# ES_Daisy_Patch_Rev4.net
KiCad netlist of a schematic drawn in EAGLE
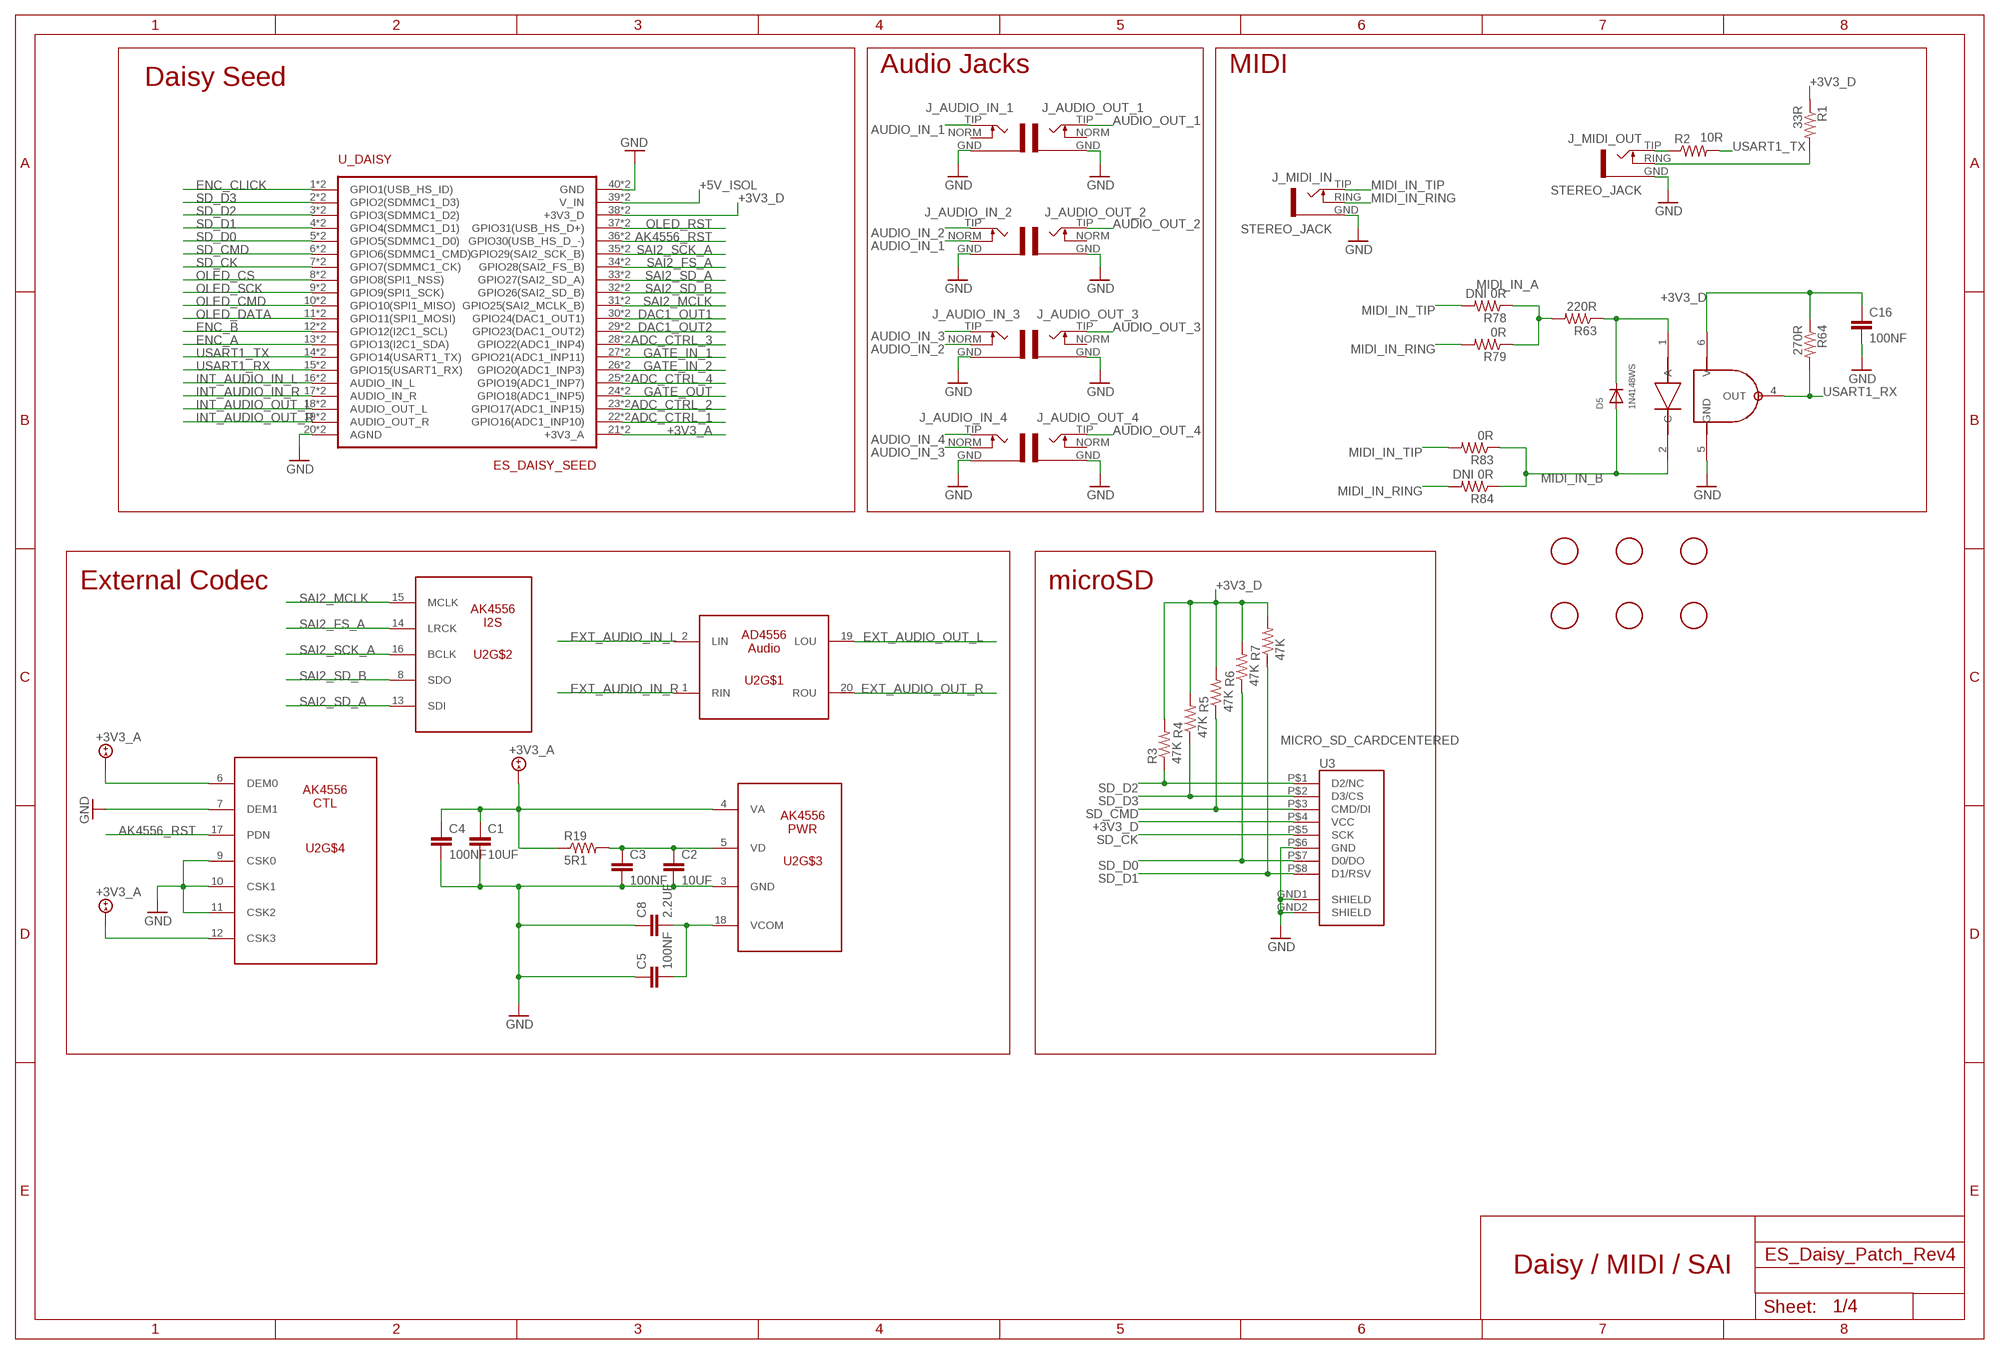
[diagram p0: schematic, sheet 1]
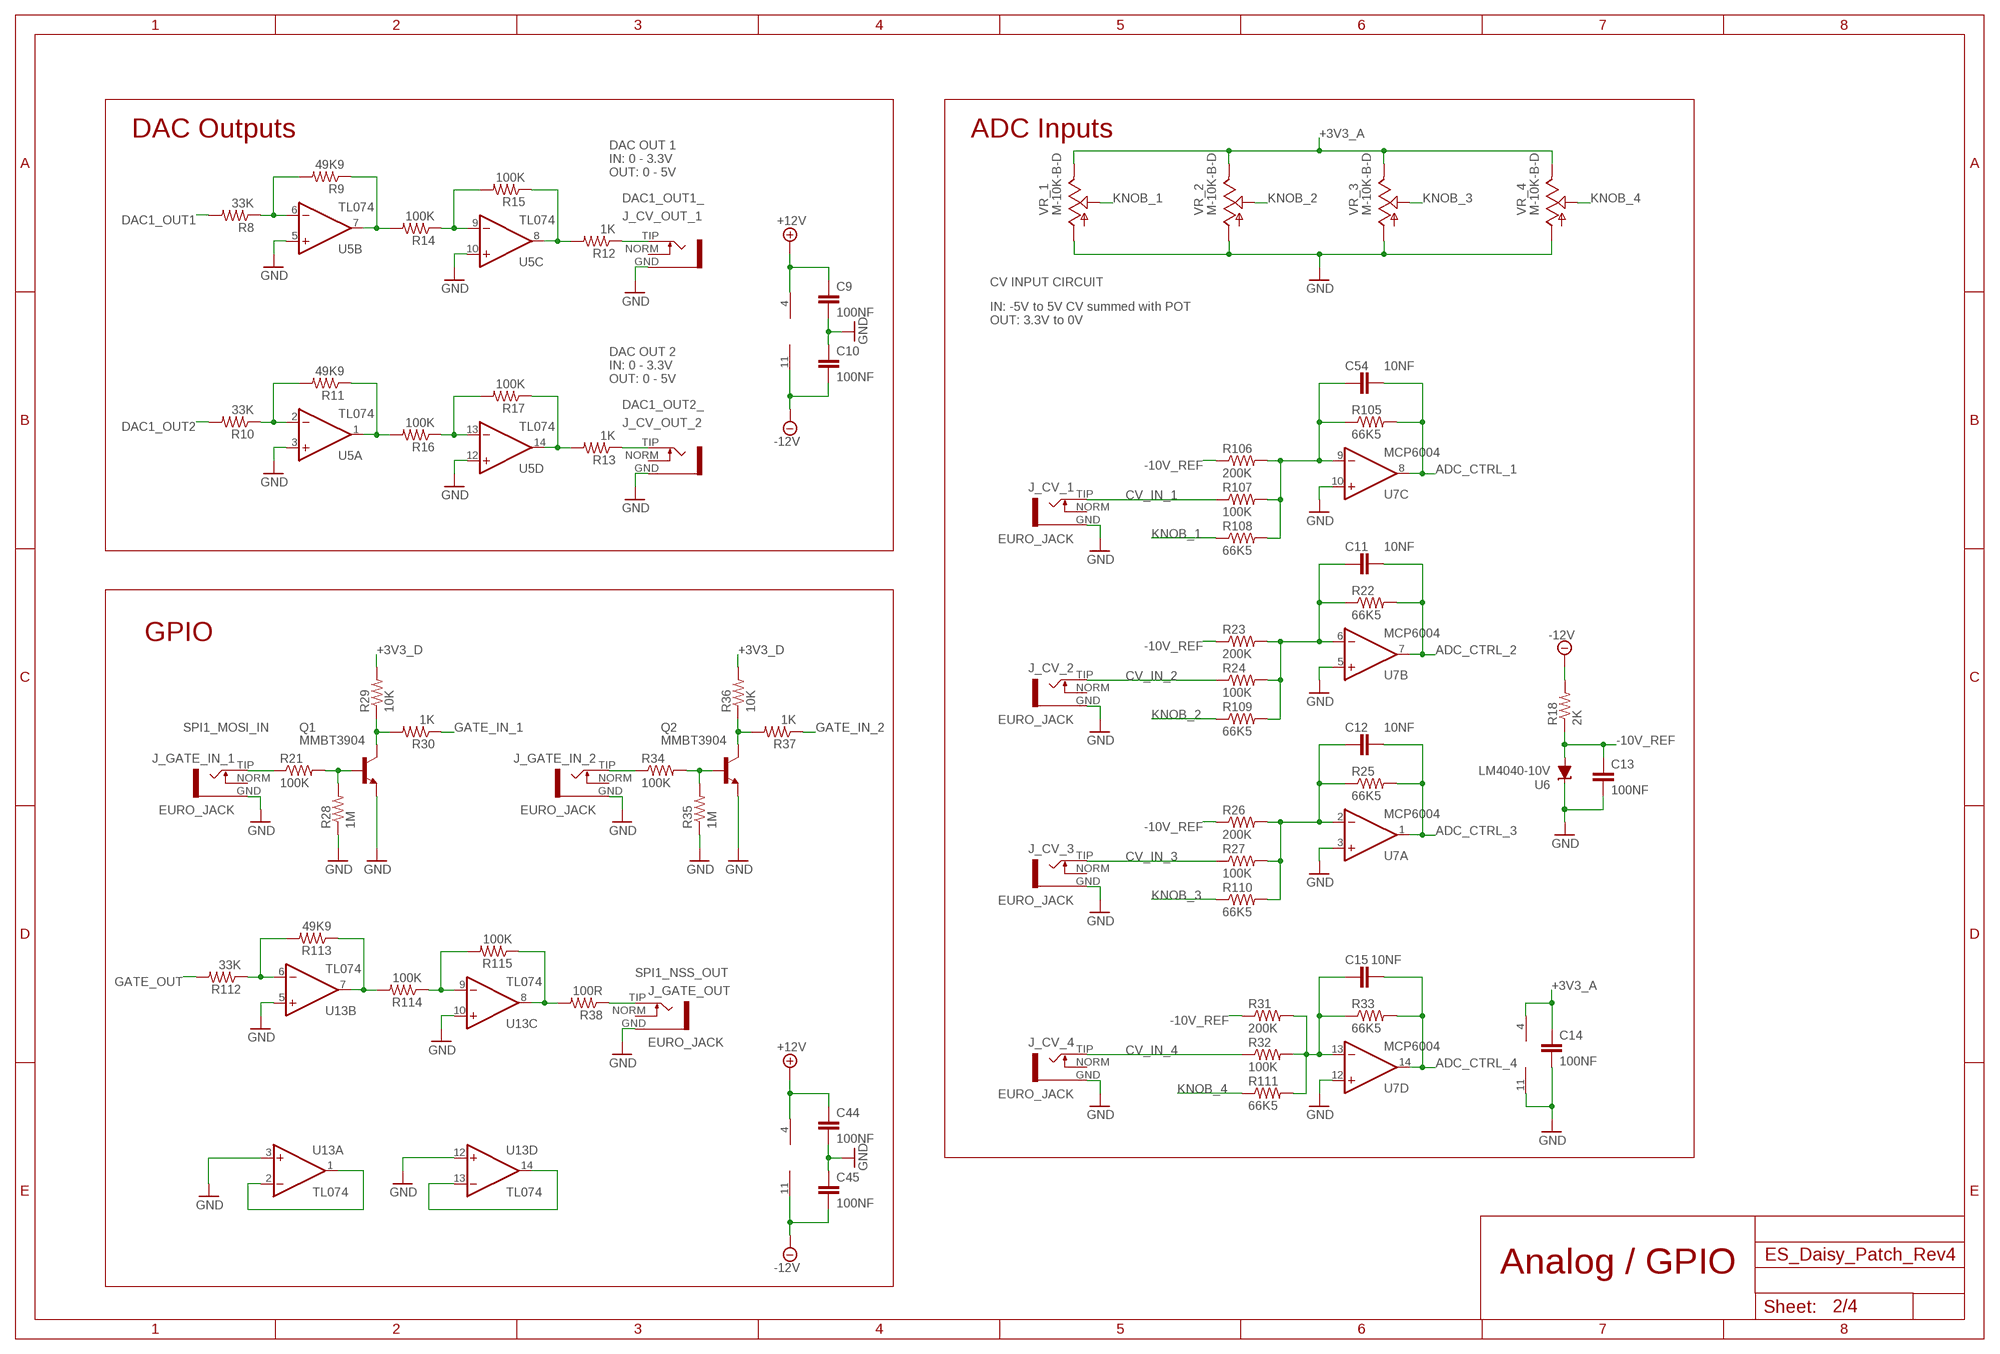
[diagram p1: schematic, sheet 2]
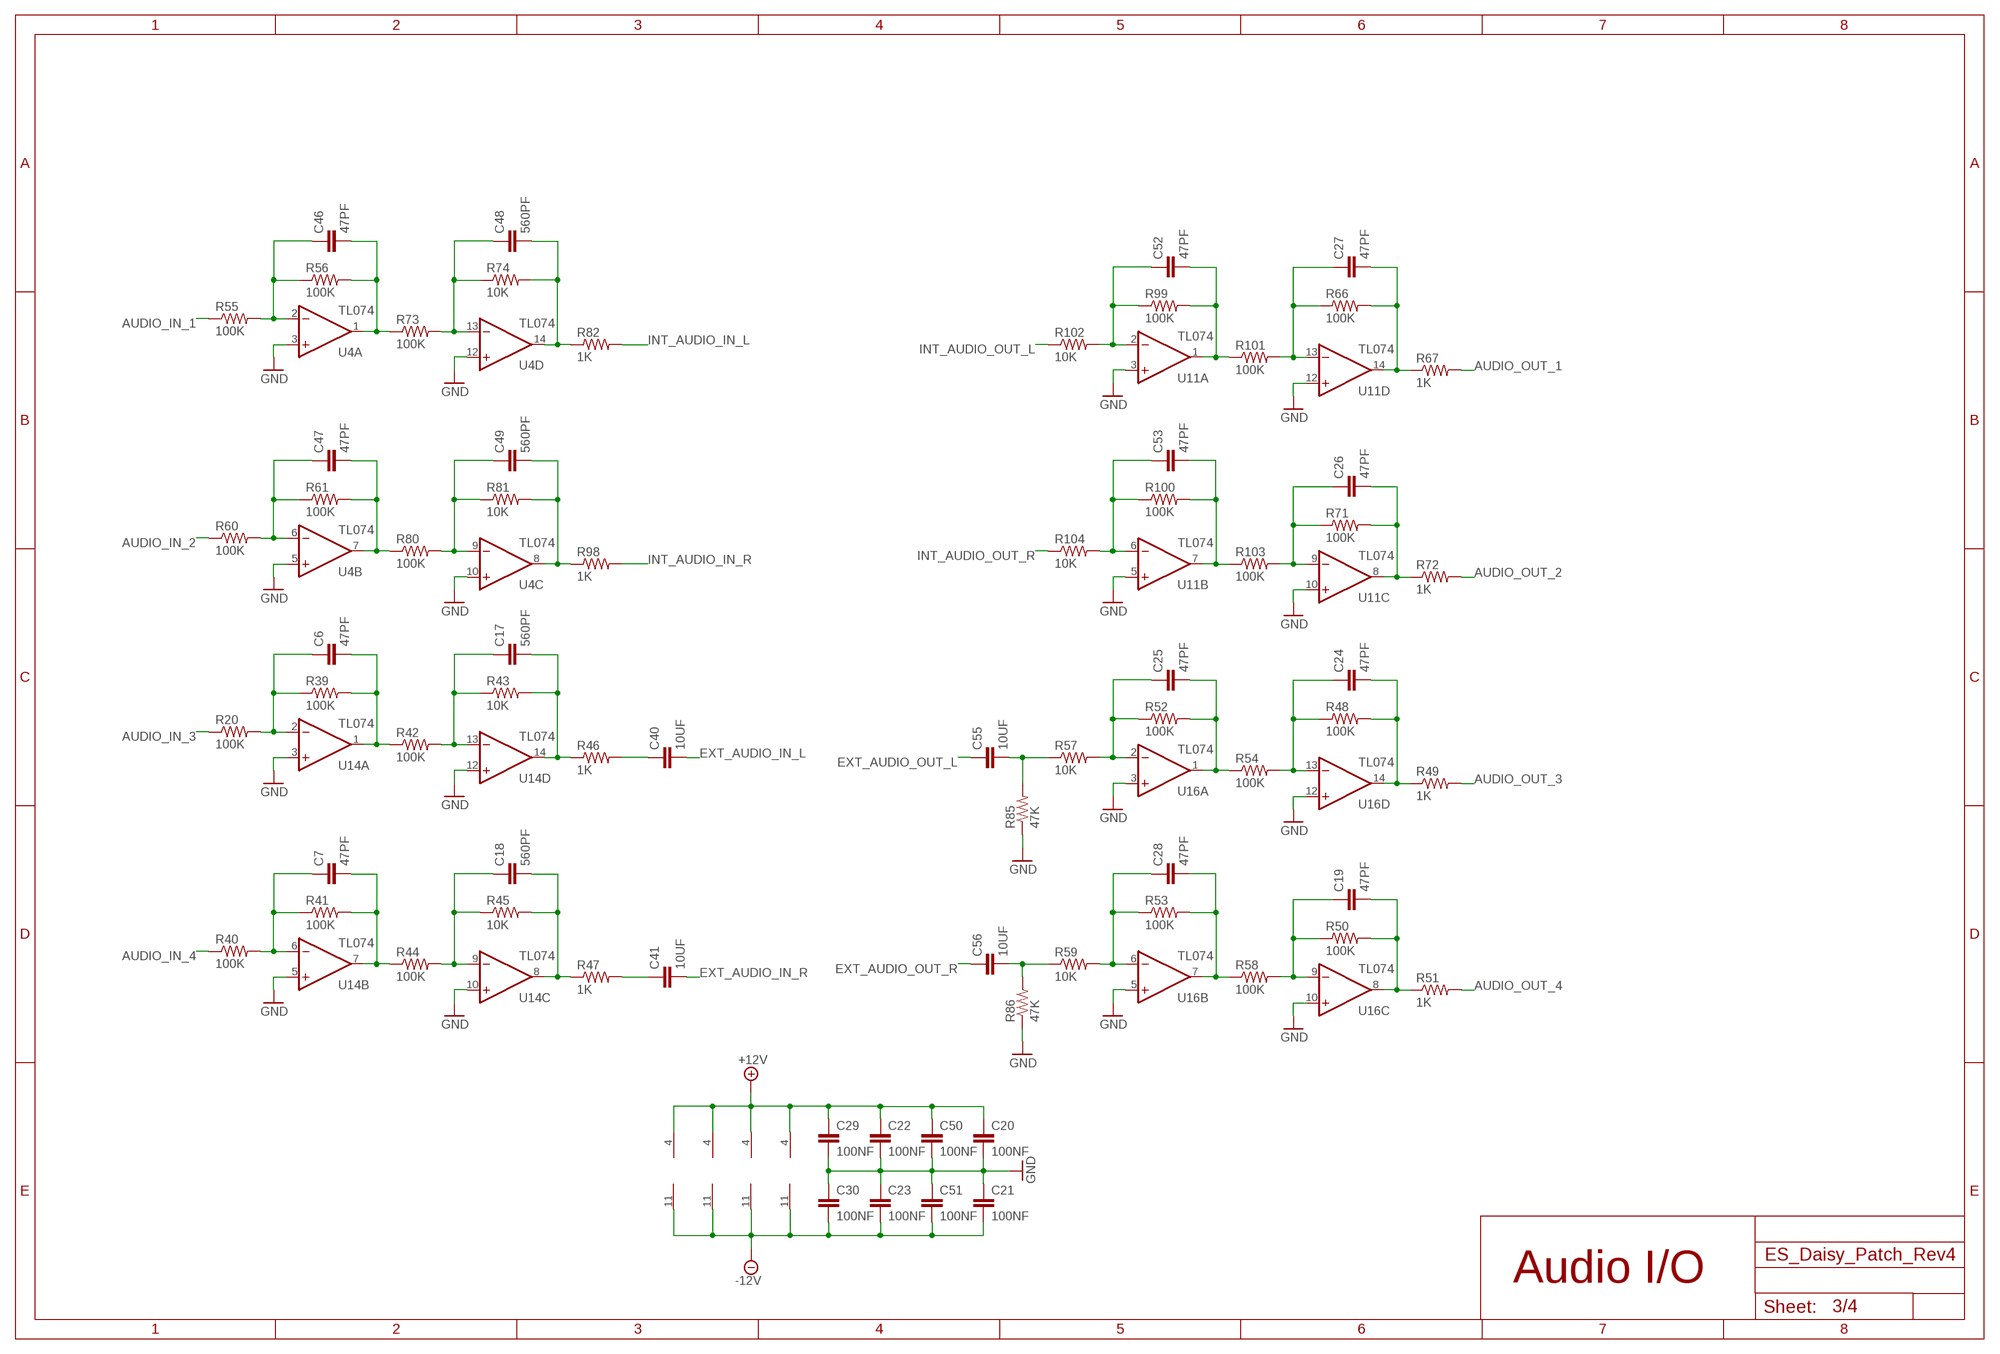
[diagram p2: schematic, sheet 3]
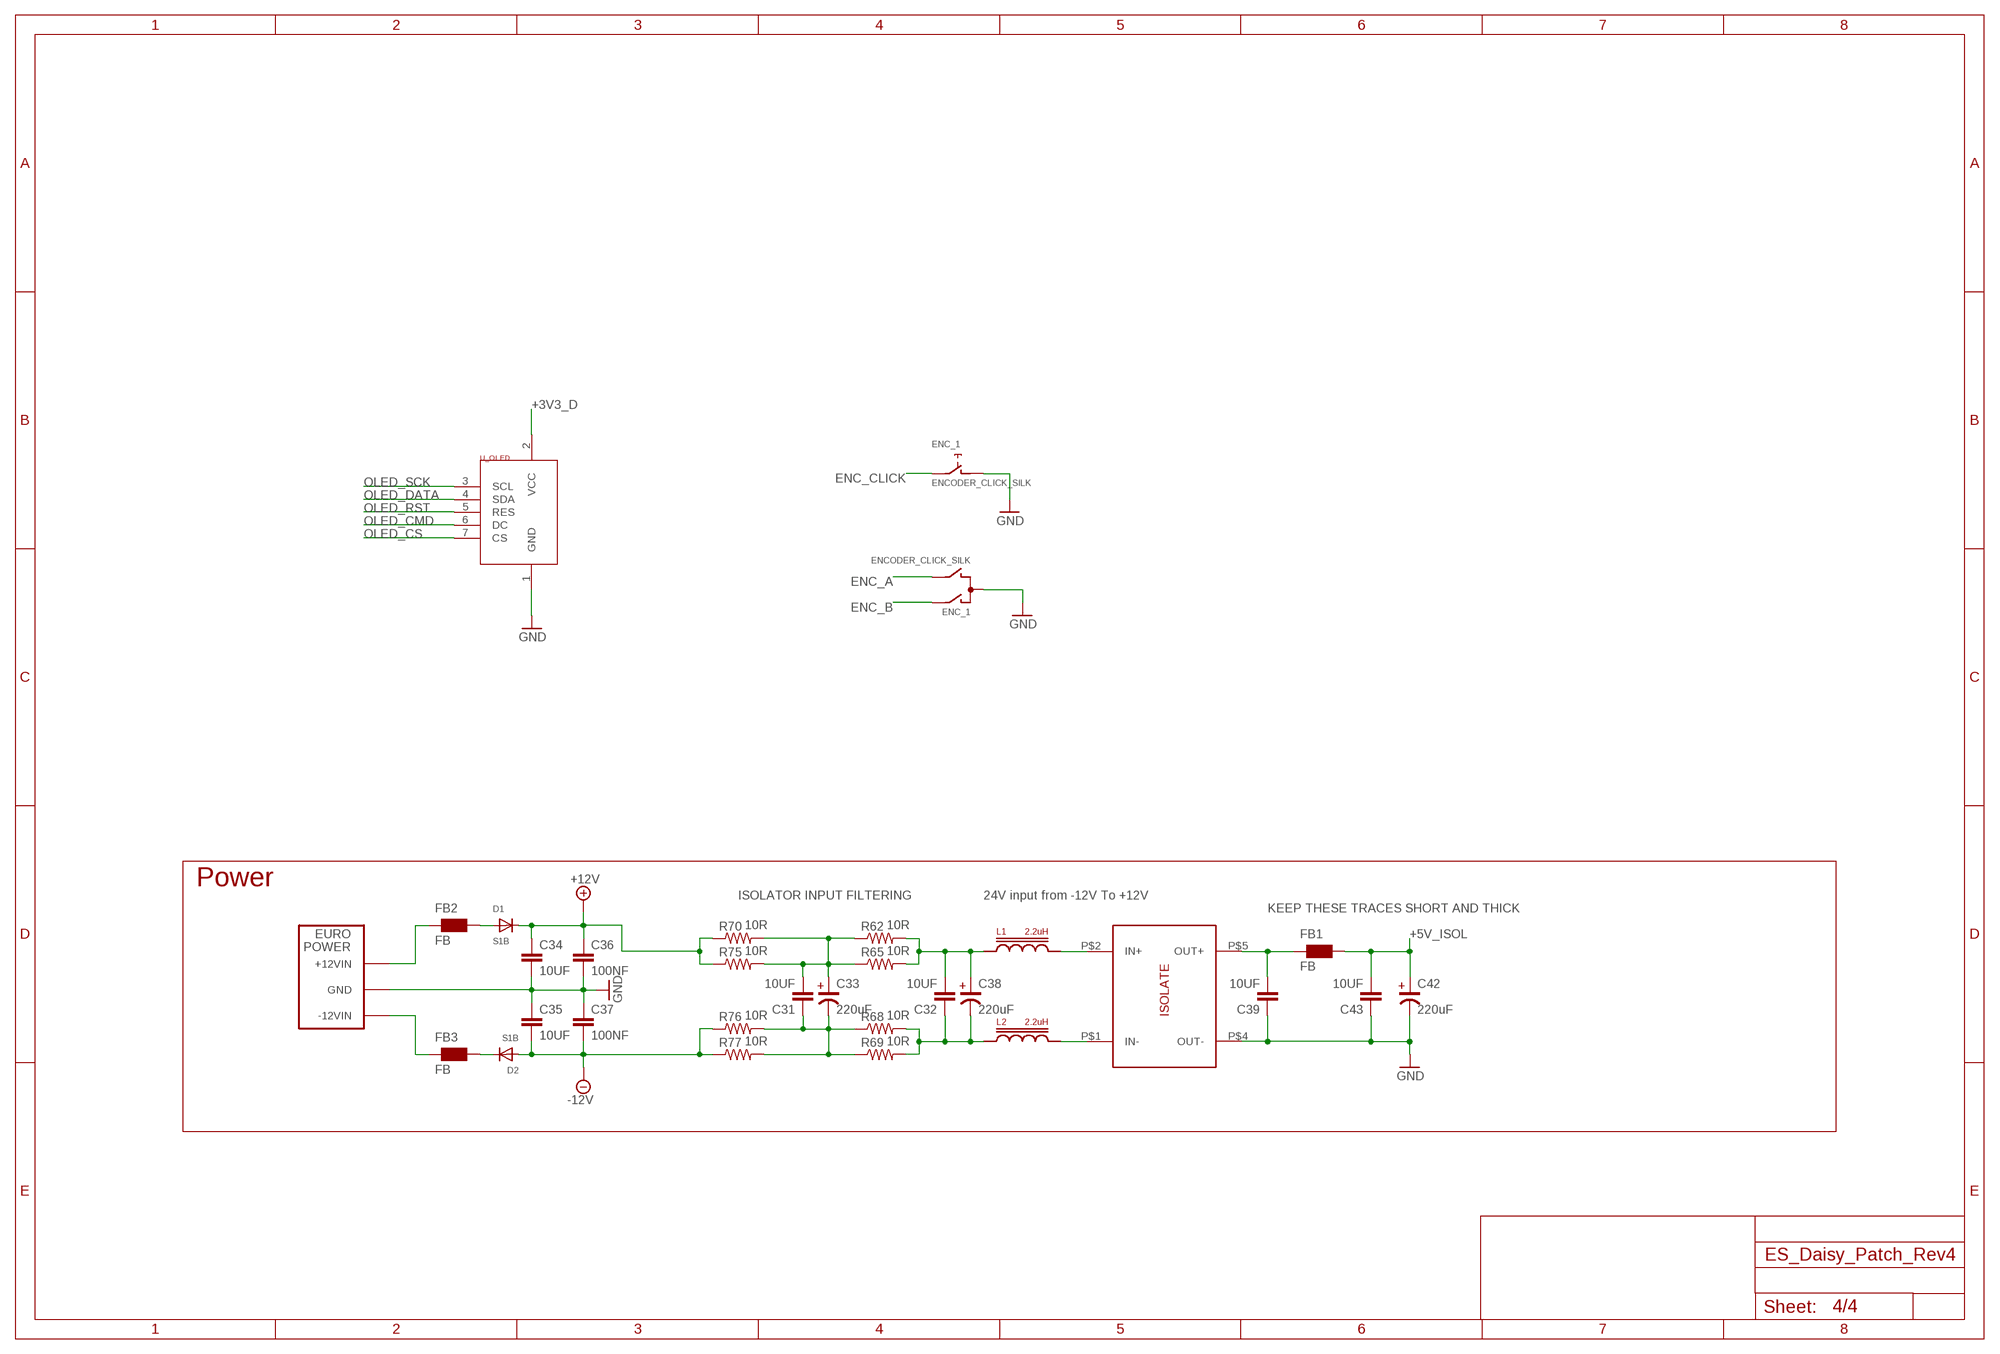
[diagram p3: schematic, sheet 4]

(export (version "E")
  (design (tool "Eeschema 10.0.6"))
  (components
    (comp (ref "C9")
      (value "100NF")
      (footprint "eagle-import:C0603")
      (libsource (lib "eagle-import") (part "C-EUC0603"))
    )
    (comp (ref "C10")
      (value "100NF")
      (footprint "eagle-import:C0603")
      (libsource (lib "eagle-import") (part "C-EUC0603"))
    )
    (comp (ref "C11")
      (value "10NF")
      (footprint "eagle-import:C0603")
      (libsource (lib "eagle-import") (part "C-EUC0603"))
    )
    (comp (ref "C12")
      (value "10NF")
      (footprint "eagle-import:C0603")
      (libsource (lib "eagle-import") (part "C-EUC0603"))
    )
    (comp (ref "C13")
      (value "100NF")
      (footprint "eagle-import:C0603")
      (libsource (lib "eagle-import") (part "C-EUC0603"))
    )
    (comp (ref "C14")
      (value "100NF")
      (footprint "eagle-import:C0603")
      (libsource (lib "eagle-import") (part "C-EUC0603"))
    )
    (comp (ref "C15")
      (value "10NF")
      (footprint "eagle-import:C0603")
      (libsource (lib "eagle-import") (part "C-EUC0603"))
    )
    (comp (ref "C44")
      (value "100NF")
      (footprint "eagle-import:C0603")
      (libsource (lib "eagle-import") (part "C-EUC0603"))
    )
    (comp (ref "C45")
      (value "100NF")
      (footprint "eagle-import:C0603")
      (libsource (lib "eagle-import") (part "C-EUC0603"))
    )
    (comp (ref "C54")
      (value "10NF")
      (footprint "eagle-import:C0603")
      (libsource (lib "eagle-import") (part "C-EUC0603"))
    )
    (comp (ref "J_CV_1")
      (value "EURO_JACK")
      (footprint "eagle-import:S_JACK")
      (libsource (lib "eagle-import") (part "EURO_JACK"))
    )
    (comp (ref "J_CV_2")
      (value "EURO_JACK")
      (footprint "eagle-import:S_JACK")
      (libsource (lib "eagle-import") (part "EURO_JACK"))
    )
    (comp (ref "J_CV_3")
      (value "EURO_JACK")
      (footprint "eagle-import:S_JACK")
      (libsource (lib "eagle-import") (part "EURO_JACK"))
    )
    (comp (ref "J_CV_4")
      (value "EURO_JACK")
      (footprint "eagle-import:S_JACK")
      (libsource (lib "eagle-import") (part "EURO_JACK"))
    )
    (comp (ref "J_CV_OUT_1")
      (value "EURO_JACK")
      (footprint "eagle-import:S_JACK")
      (libsource (lib "eagle-import") (part "EURO_JACK"))
    )
    (comp (ref "J_CV_OUT_2")
      (value "EURO_JACK")
      (footprint "eagle-import:S_JACK")
      (libsource (lib "eagle-import") (part "EURO_JACK"))
    )
    (comp (ref "J_GATE_IN_1")
      (value "EURO_JACK")
      (footprint "eagle-import:S_JACK")
      (libsource (lib "eagle-import") (part "EURO_JACK"))
    )
    (comp (ref "J_GATE_IN_2")
      (value "EURO_JACK")
      (footprint "eagle-import:S_JACK")
      (libsource (lib "eagle-import") (part "EURO_JACK"))
    )
    (comp (ref "J_GATE_OUT")
      (value "EURO_JACK")
      (footprint "eagle-import:S_JACK")
      (libsource (lib "eagle-import") (part "EURO_JACK"))
    )
    (comp (ref "Q1")
      (value "MMBT3904")
      (footprint "eagle-import:SOT23-BEC")
      (libsource (lib "eagle-import") (part "NPNSOT23-BEC"))
    )
    (comp (ref "Q2")
      (value "MMBT3904")
      (footprint "eagle-import:SOT23-BEC")
      (libsource (lib "eagle-import") (part "NPNSOT23-BEC"))
    )
    (comp (ref "R8")
      (value "33K")
      (footprint "eagle-import:R0603")
      (libsource (lib "eagle-import") (part "R-US_R0603"))
    )
    (comp (ref "R9")
      (value "49K9")
      (footprint "eagle-import:R0603")
      (libsource (lib "eagle-import") (part "R-US_R0603"))
    )
    (comp (ref "R10")
      (value "33K")
      (footprint "eagle-import:R0603")
      (libsource (lib "eagle-import") (part "R-US_R0603"))
    )
    (comp (ref "R11")
      (value "49K9")
      (footprint "eagle-import:R0603")
      (libsource (lib "eagle-import") (part "R-US_R0603"))
    )
    (comp (ref "R12")
      (value "1K")
      (footprint "eagle-import:R0603")
      (libsource (lib "eagle-import") (part "R-US_R0603"))
    )
    (comp (ref "R13")
      (value "1K")
      (footprint "eagle-import:R0603")
      (libsource (lib "eagle-import") (part "R-US_R0603"))
    )
    (comp (ref "R14")
      (value "100K")
      (footprint "eagle-import:R0603")
      (libsource (lib "eagle-import") (part "R-US_R0603"))
    )
    (comp (ref "R15")
      (value "100K")
      (footprint "eagle-import:R0603")
      (libsource (lib "eagle-import") (part "R-US_R0603"))
    )
    (comp (ref "R16")
      (value "100K")
      (footprint "eagle-import:R0603")
      (libsource (lib "eagle-import") (part "R-US_R0603"))
    )
    (comp (ref "R17")
      (value "100K")
      (footprint "eagle-import:R0603")
      (libsource (lib "eagle-import") (part "R-US_R0603"))
    )
    (comp (ref "R18")
      (value "2K")
      (footprint "eagle-import:R0603")
      (libsource (lib "eagle-import") (part "R-US_R0603"))
    )
    (comp (ref "R21")
      (value "100K")
      (footprint "eagle-import:R0603")
      (libsource (lib "eagle-import") (part "R-US_R0603"))
    )
    (comp (ref "R22")
      (value "66K5")
      (footprint "eagle-import:R0603")
      (libsource (lib "eagle-import") (part "R-US_R0603"))
    )
    (comp (ref "R23")
      (value "200K")
      (footprint "eagle-import:R0603")
      (libsource (lib "eagle-import") (part "R-US_R0603"))
    )
    (comp (ref "R24")
      (value "100K")
      (footprint "eagle-import:R0603")
      (libsource (lib "eagle-import") (part "R-US_R0603"))
    )
    (comp (ref "R25")
      (value "66K5")
      (footprint "eagle-import:R0603")
      (libsource (lib "eagle-import") (part "R-US_R0603"))
    )
    (comp (ref "R26")
      (value "200K")
      (footprint "eagle-import:R0603")
      (libsource (lib "eagle-import") (part "R-US_R0603"))
    )
    (comp (ref "R27")
      (value "100K")
      (footprint "eagle-import:R0603")
      (libsource (lib "eagle-import") (part "R-US_R0603"))
    )
    (comp (ref "R28")
      (value "1M")
      (footprint "eagle-import:R0603")
      (libsource (lib "eagle-import") (part "R-US_R0603"))
    )
    (comp (ref "R29")
      (value "10K")
      (footprint "eagle-import:R0603")
      (libsource (lib "eagle-import") (part "R-US_R0603"))
    )
    (comp (ref "R30")
      (value "1K")
      (footprint "eagle-import:R0603")
      (libsource (lib "eagle-import") (part "R-US_R0603"))
    )
    (comp (ref "R31")
      (value "200K")
      (footprint "eagle-import:R0603")
      (libsource (lib "eagle-import") (part "R-US_R0603"))
    )
    (comp (ref "R32")
      (value "100K")
      (footprint "eagle-import:R0603")
      (libsource (lib "eagle-import") (part "R-US_R0603"))
    )
    (comp (ref "R33")
      (value "66K5")
      (footprint "eagle-import:R0603")
      (libsource (lib "eagle-import") (part "R-US_R0603"))
    )
    (comp (ref "R34")
      (value "100K")
      (footprint "eagle-import:R0603")
      (libsource (lib "eagle-import") (part "R-US_R0603"))
    )
    (comp (ref "R35")
      (value "1M")
      (footprint "eagle-import:R0603")
      (libsource (lib "eagle-import") (part "R-US_R0603"))
    )
    (comp (ref "R36")
      (value "10K")
      (footprint "eagle-import:R0603")
      (libsource (lib "eagle-import") (part "R-US_R0603"))
    )
    (comp (ref "R37")
      (value "1K")
      (footprint "eagle-import:R0603")
      (libsource (lib "eagle-import") (part "R-US_R0603"))
    )
    (comp (ref "R38")
      (value "100R")
      (footprint "eagle-import:R0603")
      (libsource (lib "eagle-import") (part "R-US_R0603"))
    )
    (comp (ref "R105")
      (value "66K5")
      (footprint "eagle-import:R0603")
      (libsource (lib "eagle-import") (part "R-US_R0603"))
    )
    (comp (ref "R106")
      (value "200K")
      (footprint "eagle-import:R0603")
      (libsource (lib "eagle-import") (part "R-US_R0603"))
    )
    (comp (ref "R107")
      (value "100K")
      (footprint "eagle-import:R0603")
      (libsource (lib "eagle-import") (part "R-US_R0603"))
    )
    (comp (ref "R108")
      (value "66K5")
      (footprint "eagle-import:R0603")
      (libsource (lib "eagle-import") (part "R-US_R0603"))
    )
    (comp (ref "R109")
      (value "66K5")
      (footprint "eagle-import:R0603")
      (libsource (lib "eagle-import") (part "R-US_R0603"))
    )
    (comp (ref "R110")
      (value "66K5")
      (footprint "eagle-import:R0603")
      (libsource (lib "eagle-import") (part "R-US_R0603"))
    )
    (comp (ref "R111")
      (value "66K5")
      (footprint "eagle-import:R0603")
      (libsource (lib "eagle-import") (part "R-US_R0603"))
    )
    (comp (ref "R112")
      (value "33K")
      (footprint "eagle-import:R0603")
      (libsource (lib "eagle-import") (part "R-US_R0603"))
    )
    (comp (ref "R113")
      (value "49K9")
      (footprint "eagle-import:R0603")
      (libsource (lib "eagle-import") (part "R-US_R0603"))
    )
    (comp (ref "R114")
      (value "100K")
      (footprint "eagle-import:R0603")
      (libsource (lib "eagle-import") (part "R-US_R0603"))
    )
    (comp (ref "R115")
      (value "100K")
      (footprint "eagle-import:R0603")
      (libsource (lib "eagle-import") (part "R-US_R0603"))
    )
    (comp (ref "U5")
      (value "TL074")
      (footprint "eagle-import:TSSOP-14")
      (fields (field (name "MPN") "TL074CPWR"))
      (libsource (lib "eagle-import") (part "TL074_TSSOP-14"))
    )
    (comp (ref "U6")
      (value "LM4040-10V")
      (footprint "eagle-import:DBZ_R-PDSO-G3")
      (fields (field (name "MPN") "LM4041A12IDBZR"))
      (libsource (lib "eagle-import") (part "LM4040-10VDBZA12"))
    )
    (comp (ref "U7")
      (value "MCP6004")
      (footprint "eagle-import:TSSOP-14")
      (fields (field (name "MPN") "MCP6004T-E/ST"))
      (libsource (lib "eagle-import") (part "MCP6004_TSSOP-14"))
    )
    (comp (ref "U13")
      (value "TL074")
      (footprint "eagle-import:TSSOP-14")
      (fields (field (name "MPN") "TL074CPWR"))
      (libsource (lib "eagle-import") (part "TL074_TSSOP-14"))
    )
    (comp (ref "VR_1")
      (value "M-10K-B-D")
      (footprint "eagle-import:9MM_SNAP-IN_POT_SILK")
      (libsource (lib "eagle-import") (part "POT_9MM_SNAP-IN__"))
    )
    (comp (ref "VR_2")
      (value "M-10K-B-D")
      (footprint "eagle-import:9MM_SNAP-IN_POT_SILK")
      (libsource (lib "eagle-import") (part "POT_9MM_SNAP-IN__"))
    )
    (comp (ref "VR_3")
      (value "M-10K-B-D")
      (footprint "eagle-import:9MM_SNAP-IN_POT_SILK")
      (libsource (lib "eagle-import") (part "POT_9MM_SNAP-IN__"))
    )
    (comp (ref "VR_4")
      (value "M-10K-B-D")
      (footprint "eagle-import:9MM_SNAP-IN_POT_SILK")
      (libsource (lib "eagle-import") (part "POT_9MM_SNAP-IN__"))
    )
    (comp (ref "C6")
      (value "47PF")
      (footprint "eagle-import:C0603")
      (libsource (lib "eagle-import") (part "C-EUC0603"))
    )
    (comp (ref "C7")
      (value "47PF")
      (footprint "eagle-import:C0603")
      (libsource (lib "eagle-import") (part "C-EUC0603"))
    )
    (comp (ref "C17")
      (value "560PF")
      (footprint "eagle-import:C0603")
      (libsource (lib "eagle-import") (part "C-EUC0603"))
    )
    (comp (ref "C18")
      (value "560PF")
      (footprint "eagle-import:C0603")
      (libsource (lib "eagle-import") (part "C-EUC0603"))
    )
    (comp (ref "C19")
      (value "47PF")
      (footprint "eagle-import:C0603")
      (libsource (lib "eagle-import") (part "C-EUC0603"))
    )
    (comp (ref "C20")
      (value "100NF")
      (footprint "eagle-import:C0603")
      (libsource (lib "eagle-import") (part "C-EUC0603"))
    )
    (comp (ref "C21")
      (value "100NF")
      (footprint "eagle-import:C0603")
      (libsource (lib "eagle-import") (part "C-EUC0603"))
    )
    (comp (ref "C22")
      (value "100NF")
      (footprint "eagle-import:C0603")
      (libsource (lib "eagle-import") (part "C-EUC0603"))
    )
    (comp (ref "C23")
      (value "100NF")
      (footprint "eagle-import:C0603")
      (libsource (lib "eagle-import") (part "C-EUC0603"))
    )
    (comp (ref "C24")
      (value "47PF")
      (footprint "eagle-import:C0603")
      (libsource (lib "eagle-import") (part "C-EUC0603"))
    )
    (comp (ref "C25")
      (value "47PF")
      (footprint "eagle-import:C0603")
      (libsource (lib "eagle-import") (part "C-EUC0603"))
    )
    (comp (ref "C26")
      (value "47PF")
      (footprint "eagle-import:C0603")
      (libsource (lib "eagle-import") (part "C-EUC0603"))
    )
    (comp (ref "C27")
      (value "47PF")
      (footprint "eagle-import:C0603")
      (libsource (lib "eagle-import") (part "C-EUC0603"))
    )
    (comp (ref "C28")
      (value "47PF")
      (footprint "eagle-import:C0603")
      (libsource (lib "eagle-import") (part "C-EUC0603"))
    )
    (comp (ref "C29")
      (value "100NF")
      (footprint "eagle-import:C0603")
      (libsource (lib "eagle-import") (part "C-EUC0603"))
    )
    (comp (ref "C30")
      (value "100NF")
      (footprint "eagle-import:C0603")
      (libsource (lib "eagle-import") (part "C-EUC0603"))
    )
    (comp (ref "C40")
      (value "10UF")
      (footprint "eagle-import:C0805")
      (libsource (lib "eagle-import") (part "C-EUC0805"))
    )
    (comp (ref "C41")
      (value "10UF")
      (footprint "eagle-import:C0805")
      (libsource (lib "eagle-import") (part "C-EUC0805"))
    )
    (comp (ref "C46")
      (value "47PF")
      (footprint "eagle-import:C0603")
      (libsource (lib "eagle-import") (part "C-EUC0603"))
    )
    (comp (ref "C47")
      (value "47PF")
      (footprint "eagle-import:C0603")
      (libsource (lib "eagle-import") (part "C-EUC0603"))
    )
    (comp (ref "C48")
      (value "560PF")
      (footprint "eagle-import:C0603")
      (libsource (lib "eagle-import") (part "C-EUC0603"))
    )
    (comp (ref "C49")
      (value "560PF")
      (footprint "eagle-import:C0603")
      (libsource (lib "eagle-import") (part "C-EUC0603"))
    )
    (comp (ref "C50")
      (value "100NF")
      (footprint "eagle-import:C0603")
      (libsource (lib "eagle-import") (part "C-EUC0603"))
    )
    (comp (ref "C51")
      (value "100NF")
      (footprint "eagle-import:C0603")
      (libsource (lib "eagle-import") (part "C-EUC0603"))
    )
    (comp (ref "C52")
      (value "47PF")
      (footprint "eagle-import:C0603")
      (libsource (lib "eagle-import") (part "C-EUC0603"))
    )
    (comp (ref "C53")
      (value "47PF")
      (footprint "eagle-import:C0603")
      (libsource (lib "eagle-import") (part "C-EUC0603"))
    )
    (comp (ref "C55")
      (value "10UF")
      (footprint "eagle-import:C0805")
      (libsource (lib "eagle-import") (part "C-EUC0805"))
    )
    (comp (ref "C56")
      (value "10UF")
      (footprint "eagle-import:C0805")
      (libsource (lib "eagle-import") (part "C-EUC0805"))
    )
    (comp (ref "R20")
      (value "100K")
      (footprint "eagle-import:R0603")
      (libsource (lib "eagle-import") (part "R-US_R0603"))
    )
    (comp (ref "R39")
      (value "100K")
      (footprint "eagle-import:R0603")
      (libsource (lib "eagle-import") (part "R-US_R0603"))
    )
    (comp (ref "R40")
      (value "100K")
      (footprint "eagle-import:R0603")
      (libsource (lib "eagle-import") (part "R-US_R0603"))
    )
    (comp (ref "R41")
      (value "100K")
      (footprint "eagle-import:R0603")
      (libsource (lib "eagle-import") (part "R-US_R0603"))
    )
    (comp (ref "R42")
      (value "100K")
      (footprint "eagle-import:R0603")
      (libsource (lib "eagle-import") (part "R-US_R0603"))
    )
    (comp (ref "R43")
      (value "10K")
      (footprint "eagle-import:R0603")
      (libsource (lib "eagle-import") (part "R-US_R0603"))
    )
    (comp (ref "R44")
      (value "100K")
      (footprint "eagle-import:R0603")
      (libsource (lib "eagle-import") (part "R-US_R0603"))
    )
    (comp (ref "R45")
      (value "10K")
      (footprint "eagle-import:R0603")
      (libsource (lib "eagle-import") (part "R-US_R0603"))
    )
    (comp (ref "R46")
      (value "1K")
      (footprint "eagle-import:R0603")
      (libsource (lib "eagle-import") (part "R-US_R0603"))
    )
    (comp (ref "R47")
      (value "1K")
      (footprint "eagle-import:R0603")
      (libsource (lib "eagle-import") (part "R-US_R0603"))
    )
    (comp (ref "R48")
      (value "100K")
      (footprint "eagle-import:R0603")
      (libsource (lib "eagle-import") (part "R-US_R0603"))
    )
    (comp (ref "R49")
      (value "1K")
      (footprint "eagle-import:R0603")
      (libsource (lib "eagle-import") (part "R-US_R0603"))
    )
    (comp (ref "R50")
      (value "100K")
      (footprint "eagle-import:R0603")
      (libsource (lib "eagle-import") (part "R-US_R0603"))
    )
    (comp (ref "R51")
      (value "1K")
      (footprint "eagle-import:R0603")
      (libsource (lib "eagle-import") (part "R-US_R0603"))
    )
    (comp (ref "R52")
      (value "100K")
      (footprint "eagle-import:R0603")
      (libsource (lib "eagle-import") (part "R-US_R0603"))
    )
    (comp (ref "R53")
      (value "100K")
      (footprint "eagle-import:R0603")
      (libsource (lib "eagle-import") (part "R-US_R0603"))
    )
    (comp (ref "R54")
      (value "100K")
      (footprint "eagle-import:R0603")
      (libsource (lib "eagle-import") (part "R-US_R0603"))
    )
    (comp (ref "R55")
      (value "100K")
      (footprint "eagle-import:R0603")
      (libsource (lib "eagle-import") (part "R-US_R0603"))
    )
    (comp (ref "R56")
      (value "100K")
      (footprint "eagle-import:R0603")
      (libsource (lib "eagle-import") (part "R-US_R0603"))
    )
    (comp (ref "R57")
      (value "10K")
      (footprint "eagle-import:R0603")
      (libsource (lib "eagle-import") (part "R-US_R0603"))
    )
    (comp (ref "R58")
      (value "100K")
      (footprint "eagle-import:R0603")
      (libsource (lib "eagle-import") (part "R-US_R0603"))
    )
    (comp (ref "R59")
      (value "10K")
      (footprint "eagle-import:R0603")
      (libsource (lib "eagle-import") (part "R-US_R0603"))
    )
    (comp (ref "R60")
      (value "100K")
      (footprint "eagle-import:R0603")
      (libsource (lib "eagle-import") (part "R-US_R0603"))
    )
    (comp (ref "R61")
      (value "100K")
      (footprint "eagle-import:R0603")
      (libsource (lib "eagle-import") (part "R-US_R0603"))
    )
    (comp (ref "R66")
      (value "100K")
      (footprint "eagle-import:R0603")
      (libsource (lib "eagle-import") (part "R-US_R0603"))
    )
    (comp (ref "R67")
      (value "1K")
      (footprint "eagle-import:R0603")
      (libsource (lib "eagle-import") (part "R-US_R0603"))
    )
    (comp (ref "R71")
      (value "100K")
      (footprint "eagle-import:R0603")
      (libsource (lib "eagle-import") (part "R-US_R0603"))
    )
    (comp (ref "R72")
      (value "1K")
      (footprint "eagle-import:R0603")
      (libsource (lib "eagle-import") (part "R-US_R0603"))
    )
    (comp (ref "R73")
      (value "100K")
      (footprint "eagle-import:R0603")
      (libsource (lib "eagle-import") (part "R-US_R0603"))
    )
    (comp (ref "R74")
      (value "10K")
      (footprint "eagle-import:R0603")
      (libsource (lib "eagle-import") (part "R-US_R0603"))
    )
    (comp (ref "R80")
      (value "100K")
      (footprint "eagle-import:R0603")
      (libsource (lib "eagle-import") (part "R-US_R0603"))
    )
    (comp (ref "R81")
      (value "10K")
      (footprint "eagle-import:R0603")
      (libsource (lib "eagle-import") (part "R-US_R0603"))
    )
    (comp (ref "R82")
      (value "1K")
      (footprint "eagle-import:R0603")
      (libsource (lib "eagle-import") (part "R-US_R0603"))
    )
    (comp (ref "R85")
      (value "47K")
      (footprint "eagle-import:R0603")
      (libsource (lib "eagle-import") (part "R-US_R0603"))
    )
    (comp (ref "R86")
      (value "47K")
      (footprint "eagle-import:R0603")
      (libsource (lib "eagle-import") (part "R-US_R0603"))
    )
    (comp (ref "R98")
      (value "1K")
      (footprint "eagle-import:R0603")
      (libsource (lib "eagle-import") (part "R-US_R0603"))
    )
    (comp (ref "R99")
      (value "100K")
      (footprint "eagle-import:R0603")
      (libsource (lib "eagle-import") (part "R-US_R0603"))
    )
    (comp (ref "R100")
      (value "100K")
      (footprint "eagle-import:R0603")
      (libsource (lib "eagle-import") (part "R-US_R0603"))
    )
    (comp (ref "R101")
      (value "100K")
      (footprint "eagle-import:R0603")
      (libsource (lib "eagle-import") (part "R-US_R0603"))
    )
    (comp (ref "R102")
      (value "10K")
      (footprint "eagle-import:R0603")
      (libsource (lib "eagle-import") (part "R-US_R0603"))
    )
    (comp (ref "R103")
      (value "100K")
      (footprint "eagle-import:R0603")
      (libsource (lib "eagle-import") (part "R-US_R0603"))
    )
    (comp (ref "R104")
      (value "10K")
      (footprint "eagle-import:R0603")
      (libsource (lib "eagle-import") (part "R-US_R0603"))
    )
    (comp (ref "U4")
      (value "TL074")
      (footprint "eagle-import:TSSOP-14")
      (fields (field (name "MPN") "TL074CPWR"))
      (libsource (lib "eagle-import") (part "TL074_TSSOP-14"))
    )
    (comp (ref "U11")
      (value "TL074")
      (footprint "eagle-import:TSSOP-14")
      (fields (field (name "MPN") "TL074CPWR"))
      (libsource (lib "eagle-import") (part "TL074_TSSOP-14"))
    )
    (comp (ref "U14")
      (value "TL074")
      (footprint "eagle-import:TSSOP-14")
      (fields (field (name "MPN") "TL074CPWR"))
      (libsource (lib "eagle-import") (part "TL074_TSSOP-14"))
    )
    (comp (ref "U16")
      (value "TL074")
      (footprint "eagle-import:TSSOP-14")
      (fields (field (name "MPN") "TL074CPWR"))
      (libsource (lib "eagle-import") (part "TL074_TSSOP-14"))
    )
    (comp (ref "C31")
      (value "10UF")
      (footprint "eagle-import:C0805")
      (libsource (lib "eagle-import") (part "C-EUC0805"))
    )
    (comp (ref "C32")
      (value "10UF")
      (footprint "eagle-import:C0805")
      (libsource (lib "eagle-import") (part "C-EUC0805"))
    )
    (comp (ref "C33")
      (value "220uF")
      (footprint "eagle-import:PANASONIC_D")
      (libsource (lib "eagle-import") (part "C-EU-POL_D"))
    )
    (comp (ref "C34")
      (value "10UF")
      (footprint "eagle-import:C0805")
      (libsource (lib "eagle-import") (part "C-EUC0805"))
    )
    (comp (ref "C35")
      (value "10UF")
      (footprint "eagle-import:C0805")
      (libsource (lib "eagle-import") (part "C-EUC0805"))
    )
    (comp (ref "C36")
      (value "100NF")
      (footprint "eagle-import:C0603")
      (libsource (lib "eagle-import") (part "C-EUC0603"))
    )
    (comp (ref "C37")
      (value "100NF")
      (footprint "eagle-import:C0603")
      (libsource (lib "eagle-import") (part "C-EUC0603"))
    )
    (comp (ref "C38")
      (value "220uF")
      (footprint "eagle-import:PANASONIC_D")
      (libsource (lib "eagle-import") (part "C-EU-POL_D"))
    )
    (comp (ref "C39")
      (value "10UF")
      (footprint "eagle-import:C0805")
      (libsource (lib "eagle-import") (part "C-EUC0805"))
    )
    (comp (ref "C42")
      (value "220uF")
      (footprint "eagle-import:PANASONIC_D")
      (libsource (lib "eagle-import") (part "C-EU-POL_D"))
    )
    (comp (ref "C43")
      (value "10UF")
      (footprint "eagle-import:C0805")
      (libsource (lib "eagle-import") (part "C-EUC0805"))
    )
    (comp (ref "D1")
      (value "S1B")
      (footprint "eagle-import:SMADIODE")
      (libsource (lib "eagle-import") (part "S1B"))
    )
    (comp (ref "D2")
      (value "S1B")
      (footprint "eagle-import:SMADIODE")
      (libsource (lib "eagle-import") (part "S1B"))
    )
    (comp (ref "ENC_1")
      (value "ENCODER_CLICK_SILK")
      (footprint "eagle-import:PEC11_SILK")
      (libsource (lib "eagle-import") (part "ENCODERSILK_CLICK_"))
    )
    (comp (ref "EP1")
      (value "EURORACK_POWERSMT")
      (footprint "eagle-import:EURORACK_POWER_SMT")
      (fields (field (name "MANF") "FCI") (field (name "MPN") "54202-G08-05"))
      (libsource (lib "eagle-import") (part "EURORACK_POWERSMT"))
    )
    (comp (ref "FB1")
      (value "FB")
      (footprint "eagle-import:WUERTH-ELEKTRONIK_0603")
      (fields (field (name "MPN") "MI0603J601R-10"))
      (libsource (lib "eagle-import") (part "FERRITE_BEAD_0603"))
    )
    (comp (ref "FB2")
      (value "FB")
      (footprint "eagle-import:WUERTH-ELEKTRONIK_0603")
      (fields (field (name "MPN") "MI0603J601R-10"))
      (libsource (lib "eagle-import") (part "FERRITE_BEAD_0603"))
    )
    (comp (ref "FB3")
      (value "FB")
      (footprint "eagle-import:WUERTH-ELEKTRONIK_0603")
      (fields (field (name "MPN") "MI0603J601R-10"))
      (libsource (lib "eagle-import") (part "FERRITE_BEAD_0603"))
    )
    (comp (ref "L1")
      (value "2.2uH")
      (footprint "eagle-import:BOURNS_SRP2010")
      (libsource (lib "eagle-import") (part "INDUCTORS"))
    )
    (comp (ref "L2")
      (value "2.2uH")
      (footprint "eagle-import:BOURNS_SRP2010")
      (libsource (lib "eagle-import") (part "INDUCTORS"))
    )
    (comp (ref "R62")
      (value "10R")
      (footprint "eagle-import:R0603")
      (libsource (lib "eagle-import") (part "R-US_R0603"))
    )
    (comp (ref "R65")
      (value "10R")
      (footprint "eagle-import:R0603")
      (libsource (lib "eagle-import") (part "R-US_R0603"))
    )
    (comp (ref "R68")
      (value "10R")
      (footprint "eagle-import:R0603")
      (libsource (lib "eagle-import") (part "R-US_R0603"))
    )
    (comp (ref "R69")
      (value "10R")
      (footprint "eagle-import:R0603")
      (libsource (lib "eagle-import") (part "R-US_R0603"))
    )
    (comp (ref "R70")
      (value "10R")
      (footprint "eagle-import:R0603")
      (libsource (lib "eagle-import") (part "R-US_R0603"))
    )
    (comp (ref "R75")
      (value "10R")
      (footprint "eagle-import:R0603")
      (libsource (lib "eagle-import") (part "R-US_R0603"))
    )
    (comp (ref "R76")
      (value "10R")
      (footprint "eagle-import:R0603")
      (libsource (lib "eagle-import") (part "R-US_R0603"))
    )
    (comp (ref "R77")
      (value "10R")
      (footprint "eagle-import:R0603")
      (libsource (lib "eagle-import") (part "R-US_R0603"))
    )
    (comp (ref "U$1")
      (value "POWER_ISOLATE")
      (footprint "eagle-import:XP_POWER_ISEXXXXA")
      (fields (field (name "MPN") "ISE2405A"))
      (libsource (lib "eagle-import") (part "POWER_ISOLATE"))
    )
    (comp (ref "U_OLED")
      (value "OLED_DISPLAY")
      (footprint "eagle-import:ER-OLEDM015-2")
      (fields (field (name "MPN") "ER-OLEDM015-2W-SPI-I2C"))
      (libsource (lib "eagle-import") (part "OLED_DISPLAY"))
    )
    (comp (ref "C1")
      (value "10UF")
      (footprint "eagle-import:C0805")
      (libsource (lib "eagle-import") (part "C-EUC0805"))
    )
    (comp (ref "C2")
      (value "10UF")
      (footprint "eagle-import:C0805")
      (libsource (lib "eagle-import") (part "C-EUC0805"))
    )
    (comp (ref "C3")
      (value "100NF")
      (footprint "eagle-import:C0603")
      (libsource (lib "eagle-import") (part "C-EUC0603"))
    )
    (comp (ref "C4")
      (value "100NF")
      (footprint "eagle-import:C0603")
      (libsource (lib "eagle-import") (part "C-EUC0603"))
    )
    (comp (ref "C5")
      (value "100NF")
      (footprint "eagle-import:C0603")
      (libsource (lib "eagle-import") (part "C-EUC0603"))
    )
    (comp (ref "C8")
      (value "2.2UF")
      (footprint "eagle-import:C0603")
      (libsource (lib "eagle-import") (part "C-EUC0603"))
    )
    (comp (ref "C16")
      (value "100NF")
      (footprint "eagle-import:C0603")
      (libsource (lib "eagle-import") (part "C-EUC0603"))
    )
    (comp (ref "D5")
      (value "1N4148WS")
      (footprint "eagle-import:SOD-323F")
      (libsource (lib "eagle-import") (part "DIODE_SOD-323F"))
    )
    (comp (ref "FD1")
      (value "FIDUCIAL")
      (footprint "eagle-import:FIDUCIAL_1MM")
      (libsource (lib "eagle-import") (part "FIDUCIAL"))
    )
    (comp (ref "FD2")
      (value "FIDUCIAL")
      (footprint "eagle-import:FIDUCIAL_1MM")
      (libsource (lib "eagle-import") (part "FIDUCIAL"))
    )
    (comp (ref "FD3")
      (value "FIDUCIAL")
      (footprint "eagle-import:FIDUCIAL_1MM")
      (libsource (lib "eagle-import") (part "FIDUCIAL"))
    )
    (comp (ref "FD4")
      (value "FIDUCIAL")
      (footprint "eagle-import:FIDUCIAL_1MM")
      (libsource (lib "eagle-import") (part "FIDUCIAL"))
    )
    (comp (ref "FD5")
      (value "FIDUCIAL")
      (footprint "eagle-import:FIDUCIAL_1MM")
      (libsource (lib "eagle-import") (part "FIDUCIAL"))
    )
    (comp (ref "FD6")
      (value "FIDUCIAL")
      (footprint "eagle-import:FIDUCIAL_1MM")
      (libsource (lib "eagle-import") (part "FIDUCIAL"))
    )
    (comp (ref "J_AUDIO_IN_1")
      (value "EURO_JACK")
      (footprint "eagle-import:S_JACK")
      (libsource (lib "eagle-import") (part "EURO_JACK"))
    )
    (comp (ref "J_AUDIO_IN_2")
      (value "EURO_JACK")
      (footprint "eagle-import:S_JACK")
      (libsource (lib "eagle-import") (part "EURO_JACK"))
    )
    (comp (ref "J_AUDIO_IN_3")
      (value "EURO_JACK")
      (footprint "eagle-import:S_JACK")
      (libsource (lib "eagle-import") (part "EURO_JACK"))
    )
    (comp (ref "J_AUDIO_IN_4")
      (value "EURO_JACK")
      (footprint "eagle-import:S_JACK")
      (libsource (lib "eagle-import") (part "EURO_JACK"))
    )
    (comp (ref "J_AUDIO_OUT_1")
      (value "EURO_JACK")
      (footprint "eagle-import:S_JACK")
      (libsource (lib "eagle-import") (part "EURO_JACK"))
    )
    (comp (ref "J_AUDIO_OUT_2")
      (value "EURO_JACK")
      (footprint "eagle-import:S_JACK")
      (libsource (lib "eagle-import") (part "EURO_JACK"))
    )
    (comp (ref "J_AUDIO_OUT_3")
      (value "EURO_JACK")
      (footprint "eagle-import:S_JACK")
      (libsource (lib "eagle-import") (part "EURO_JACK"))
    )
    (comp (ref "J_AUDIO_OUT_4")
      (value "EURO_JACK")
      (footprint "eagle-import:S_JACK")
      (libsource (lib "eagle-import") (part "EURO_JACK"))
    )
    (comp (ref "J_MIDI_IN")
      (value "STEREO_JACK")
      (footprint "eagle-import:STEREO_JACK_3.5MM")
      (libsource (lib "eagle-import") (part "STEREO_JACK"))
    )
    (comp (ref "J_MIDI_OUT")
      (value "STEREO_JACK")
      (footprint "eagle-import:STEREO_JACK_3.5MM")
      (libsource (lib "eagle-import") (part "STEREO_JACK"))
    )
    (comp (ref "R1")
      (value "33R")
      (footprint "eagle-import:R0603")
      (libsource (lib "eagle-import") (part "R-US_R0603"))
    )
    (comp (ref "R2")
      (value "10R")
      (footprint "eagle-import:R0603")
      (libsource (lib "eagle-import") (part "R-US_R0603"))
    )
    (comp (ref "R3")
      (value "47K")
      (footprint "eagle-import:R0603")
      (libsource (lib "eagle-import") (part "R-US_R0603"))
    )
    (comp (ref "R4")
      (value "47K")
      (footprint "eagle-import:R0603")
      (libsource (lib "eagle-import") (part "R-US_R0603"))
    )
    (comp (ref "R5")
      (value "47K")
      (footprint "eagle-import:R0603")
      (libsource (lib "eagle-import") (part "R-US_R0603"))
    )
    (comp (ref "R6")
      (value "47K")
      (footprint "eagle-import:R0603")
      (libsource (lib "eagle-import") (part "R-US_R0603"))
    )
    (comp (ref "R7")
      (value "47K")
      (footprint "eagle-import:R0603")
      (libsource (lib "eagle-import") (part "R-US_R0603"))
    )
    (comp (ref "R19")
      (value "5R1")
      (footprint "eagle-import:R0603")
      (libsource (lib "eagle-import") (part "R-US_R0603"))
    )
    (comp (ref "R63")
      (value "220R")
      (footprint "eagle-import:R0603")
      (libsource (lib "eagle-import") (part "R-US_R0603"))
    )
    (comp (ref "R64")
      (value "270R")
      (footprint "eagle-import:R0603")
      (libsource (lib "eagle-import") (part "R-US_R0603"))
    )
    (comp (ref "R78")
      (value "DNI 0R")
      (footprint "eagle-import:R0603")
      (libsource (lib "eagle-import") (part "R-US_R0603"))
    )
    (comp (ref "R79")
      (value "0R")
      (footprint "eagle-import:R0603")
      (libsource (lib "eagle-import") (part "R-US_R0603"))
    )
    (comp (ref "R83")
      (value "0R")
      (footprint "eagle-import:R0603")
      (libsource (lib "eagle-import") (part "R-US_R0603"))
    )
    (comp (ref "R84")
      (value "DNI 0R")
      (footprint "eagle-import:R0603")
      (libsource (lib "eagle-import") (part "R-US_R0603"))
    )
    (comp (ref "U2")
      (value "AK4556")
      (footprint "eagle-import:TSSOP20")
      (libsource (lib "eagle-import") (part "AK4556"))
    )
    (comp (ref "U3")
      (value "MICRO_SD_CARDCENTERED")
      (footprint "eagle-import:VERT_MICROSD_CENTERED")
      (libsource (lib "eagle-import") (part "MICRO_SD_CARDCENTERED"))
    )
    (comp (ref "U15")
      (value "OPTOISOLATOR_H11L1M")
      (footprint "eagle-import:DIL06_GULLWING")
      (fields (field (name "MPN") "H11L1SR2M"))
      (libsource (lib "eagle-import") (part "OPTOISOLATOR_H11L1M"))
    )
    (comp (ref "U_DAISY")
      (value "ES_DAISY_SEED")
      (footprint "eagle-import:ES_DAISY_SEED_DOUBLE")
      (libsource (lib "eagle-import") (part "ES_DAISY_SEED_REV4_DOUBLE"))
    )
  )
  (nets
    (net (code "1") (name "+3V3_A") (class "Default")
      (node (ref "C1") (pin "1") (pinfunction "1_1") (pintype "passive"))
      (node (ref "C14") (pin "1") (pinfunction "1_1") (pintype "passive"))
      (node (ref "C4") (pin "1") (pinfunction "1_1") (pintype "passive"))
      (node (ref "R19") (pin "1") (pinfunction "1_1") (pintype "passive"))
      (node (ref "U2") (pin "12") (pinfunction "CSK3_12") (pintype "bidirectional"))
      (node (ref "U2") (pin "4") (pinfunction "VA_4") (pintype "bidirectional"))
      (node (ref "U2") (pin "6") (pinfunction "DEM0_6") (pintype "bidirectional"))
      (node (ref "U7") (pin "4") (pinfunction "V+_4") (pintype "power_in"))
      (node (ref "U_DAISY") (pin "21") (pinfunction "+3V3_A_21") (pintype "bidirectional"))
      (node (ref "U_DAISY") (pin "B21") (pinfunction "+3V3_A_B21") (pintype "bidirectional"))
      (node (ref "VR_1") (pin "3") (pinfunction "3_3") (pintype "passive"))
      (node (ref "VR_2") (pin "3") (pinfunction "3_3") (pintype "passive"))
      (node (ref "VR_3") (pin "3") (pinfunction "3_3") (pintype "passive"))
      (node (ref "VR_4") (pin "3") (pinfunction "3_3") (pintype "passive"))
    )
    (net (code "2") (name "+3V3_D") (class "Default")
      (node (ref "C16") (pin "1") (pinfunction "1_1") (pintype "passive"))
      (node (ref "R1") (pin "1") (pinfunction "1_1") (pintype "passive"))
      (node (ref "R29") (pin "2") (pinfunction "2_2") (pintype "passive"))
      (node (ref "R3") (pin "2") (pinfunction "2_2") (pintype "passive"))
      (node (ref "R36") (pin "2") (pinfunction "2_2") (pintype "passive"))
      (node (ref "R4") (pin "2") (pinfunction "2_2") (pintype "passive"))
      (node (ref "R5") (pin "2") (pinfunction "2_2") (pintype "passive"))
      (node (ref "R6") (pin "2") (pinfunction "2_2") (pintype "passive"))
      (node (ref "R64") (pin "1") (pinfunction "1_1") (pintype "passive"))
      (node (ref "R7") (pin "2") (pinfunction "2_2") (pintype "passive"))
      (node (ref "U15") (pin "6") (pinfunction "V_6") (pintype "bidirectional"))
      (node (ref "U3") (pin "P$4") (pinfunction "VCC_P$4") (pintype "bidirectional"))
      (node (ref "U_DAISY") (pin "38") (pinfunction "+3V3_D_38") (pintype "bidirectional"))
      (node (ref "U_DAISY") (pin "B38") (pinfunction "+3V3_D_B38") (pintype "bidirectional"))
      (node (ref "U_OLED") (pin "2") (pinfunction "VCC_2") (pintype "bidirectional"))
    )
    (net (code "3") (name "+5V_ISOL") (class "Default")
      (node (ref "C42") (pin "+") (pinfunction "POS_+") (pintype "passive"))
      (node (ref "C43") (pin "2") (pinfunction "2_2") (pintype "passive"))
      (node (ref "FB1") (pin "2") (pinfunction "2_2") (pintype "passive"))
      (node (ref "U_DAISY") (pin "39") (pinfunction "V_IN_39") (pintype "bidirectional"))
      (node (ref "U_DAISY") (pin "B39") (pinfunction "V_IN_B39") (pintype "bidirectional"))
    )
    (net (code "4") (name "+12V") (class "Default")
      (node (ref "C20") (pin "1") (pinfunction "1_1") (pintype "passive"))
      (node (ref "C22") (pin "1") (pinfunction "1_1") (pintype "passive"))
      (node (ref "C29") (pin "1") (pinfunction "1_1") (pintype "passive"))
      (node (ref "C34") (pin "1") (pinfunction "1_1") (pintype "passive"))
      (node (ref "C36") (pin "1") (pinfunction "1_1") (pintype "passive"))
      (node (ref "C44") (pin "1") (pinfunction "1_1") (pintype "passive"))
      (node (ref "C50") (pin "1") (pinfunction "1_1") (pintype "passive"))
      (node (ref "C9") (pin "1") (pinfunction "1_1") (pintype "passive"))
      (node (ref "D1") (pin "C") (pinfunction "C_C") (pintype "passive"))
      (node (ref "R70") (pin "1") (pinfunction "1_1") (pintype "passive"))
      (node (ref "R75") (pin "1") (pinfunction "1_1") (pintype "passive"))
      (node (ref "U11") (pin "4") (pinfunction "V+_4") (pintype "power_in"))
      (node (ref "U13") (pin "4") (pinfunction "V+_4") (pintype "power_in"))
      (node (ref "U14") (pin "4") (pinfunction "V+_4") (pintype "power_in"))
      (node (ref "U16") (pin "4") (pinfunction "V+_4") (pintype "power_in"))
      (node (ref "U4") (pin "4") (pinfunction "V+_4") (pintype "power_in"))
      (node (ref "U5") (pin "4") (pinfunction "V+_4") (pintype "power_in"))
    )
    (net (code "5") (name "-10V_REF") (class "Default")
      (node (ref "C13") (pin "1") (pinfunction "1_1") (pintype "passive"))
      (node (ref "R106") (pin "1") (pinfunction "1_1") (pintype "passive"))
      (node (ref "R18") (pin "1") (pinfunction "1_1") (pintype "passive"))
      (node (ref "R23") (pin "1") (pinfunction "1_1") (pintype "passive"))
      (node (ref "R26") (pin "1") (pinfunction "1_1") (pintype "passive"))
      (node (ref "R31") (pin "1") (pinfunction "1_1") (pintype "passive"))
      (node (ref "U6") (pin "2") (pinfunction "A_2") (pintype "passive"))
    )
    (net (code "6") (name "-12V") (class "Default")
      (node (ref "C10") (pin "2") (pinfunction "2_2") (pintype "passive"))
      (node (ref "C21") (pin "2") (pinfunction "2_2") (pintype "passive"))
      (node (ref "C23") (pin "2") (pinfunction "2_2") (pintype "passive"))
      (node (ref "C30") (pin "2") (pinfunction "2_2") (pintype "passive"))
      (node (ref "C35") (pin "2") (pinfunction "2_2") (pintype "passive"))
      (node (ref "C37") (pin "2") (pinfunction "2_2") (pintype "passive"))
      (node (ref "C45") (pin "2") (pinfunction "2_2") (pintype "passive"))
      (node (ref "C51") (pin "2") (pinfunction "2_2") (pintype "passive"))
      (node (ref "D2") (pin "A") (pinfunction "A_A") (pintype "passive"))
      (node (ref "R18") (pin "2") (pinfunction "2_2") (pintype "passive"))
      (node (ref "R76") (pin "1") (pinfunction "1_1") (pintype "passive"))
      (node (ref "R77") (pin "1") (pinfunction "1_1") (pintype "passive"))
      (node (ref "U11") (pin "11") (pinfunction "V-_11") (pintype "power_in"))
      (node (ref "U13") (pin "11") (pinfunction "V-_11") (pintype "power_in"))
      (node (ref "U14") (pin "11") (pinfunction "V-_11") (pintype "power_in"))
      (node (ref "U16") (pin "11") (pinfunction "V-_11") (pintype "power_in"))
      (node (ref "U4") (pin "11") (pinfunction "V-_11") (pintype "power_in"))
      (node (ref "U5") (pin "11") (pinfunction "V-_11") (pintype "power_in"))
    )
    (net (code "7") (name "ADC_CTRL_1") (class "Default")
      (node (ref "C54") (pin "2") (pinfunction "2_2") (pintype "passive"))
      (node (ref "R105") (pin "2") (pinfunction "2_2") (pintype "passive"))
      (node (ref "U7") (pin "8") (pinfunction "OUT_8") (pintype "output"))
      (node (ref "U_DAISY") (pin "22") (pinfunction "GPIO16(ADC1_INP10)_22") (pintype "bidirectional"))
      (node (ref "U_DAISY") (pin "B22") (pinfunction "GPIO16(ADC1_INP10)_B22") (pintype "bidirectional"))
    )
    (net (code "8") (name "ADC_CTRL_2") (class "Default")
      (node (ref "C11") (pin "2") (pinfunction "2_2") (pintype "passive"))
      (node (ref "R22") (pin "2") (pinfunction "2_2") (pintype "passive"))
      (node (ref "U7") (pin "7") (pinfunction "OUT_7") (pintype "output"))
      (node (ref "U_DAISY") (pin "23") (pinfunction "GPIO17(ADC1_INP15)_23") (pintype "bidirectional"))
      (node (ref "U_DAISY") (pin "B23") (pinfunction "GPIO17(ADC1_INP15)_B23") (pintype "bidirectional"))
    )
    (net (code "9") (name "ADC_CTRL_3") (class "Default")
      (node (ref "C12") (pin "2") (pinfunction "2_2") (pintype "passive"))
      (node (ref "R25") (pin "2") (pinfunction "2_2") (pintype "passive"))
      (node (ref "U7") (pin "1") (pinfunction "OUT_1") (pintype "output"))
      (node (ref "U_DAISY") (pin "28") (pinfunction "GPIO22(ADC1_INP4)_28") (pintype "bidirectional"))
      (node (ref "U_DAISY") (pin "B28") (pinfunction "GPIO22(ADC1_INP4)_B28") (pintype "bidirectional"))
    )
    (net (code "10") (name "ADC_CTRL_4") (class "Default")
      (node (ref "C15") (pin "2") (pinfunction "2_2") (pintype "passive"))
      (node (ref "R33") (pin "2") (pinfunction "2_2") (pintype "passive"))
      (node (ref "U7") (pin "14") (pinfunction "OUT_14") (pintype "output"))
      (node (ref "U_DAISY") (pin "25") (pinfunction "GPIO19(ADC1_INP7)_25") (pintype "bidirectional"))
      (node (ref "U_DAISY") (pin "B25") (pinfunction "GPIO19(ADC1_INP7)_B25") (pintype "bidirectional"))
    )
    (net (code "11") (name "AK4556_RST") (class "Default")
      (node (ref "U2") (pin "17") (pinfunction "PDN_17") (pintype "bidirectional"))
      (node (ref "U_DAISY") (pin "36") (pinfunction "GPIO30(USB_HS_D_-)_36") (pintype "bidirectional"))
      (node (ref "U_DAISY") (pin "B36") (pinfunction "GPIO30(USB_HS_D_-)_B36") (pintype "bidirectional"))
    )
    (net (code "12") (name "AUDIO_IN_1") (class "Default")
      (node (ref "J_AUDIO_IN_1") (pin "TIP") (pinfunction "TIP_TIP") (pintype "passive"))
      (node (ref "J_AUDIO_IN_2") (pin "NORM") (pinfunction "NORM_NORM") (pintype "passive"))
      (node (ref "R55") (pin "1") (pinfunction "1_1") (pintype "passive"))
    )
    (net (code "13") (name "AUDIO_IN_2") (class "Default")
      (node (ref "J_AUDIO_IN_2") (pin "TIP") (pinfunction "TIP_TIP") (pintype "passive"))
      (node (ref "J_AUDIO_IN_3") (pin "NORM") (pinfunction "NORM_NORM") (pintype "passive"))
      (node (ref "R60") (pin "1") (pinfunction "1_1") (pintype "passive"))
    )
    (net (code "14") (name "AUDIO_IN_3") (class "Default")
      (node (ref "J_AUDIO_IN_3") (pin "TIP") (pinfunction "TIP_TIP") (pintype "passive"))
      (node (ref "J_AUDIO_IN_4") (pin "NORM") (pinfunction "NORM_NORM") (pintype "passive"))
      (node (ref "R20") (pin "1") (pinfunction "1_1") (pintype "passive"))
    )
    (net (code "15") (name "AUDIO_IN_4") (class "Default")
      (node (ref "J_AUDIO_IN_4") (pin "TIP") (pinfunction "TIP_TIP") (pintype "passive"))
      (node (ref "R40") (pin "1") (pinfunction "1_1") (pintype "passive"))
    )
    (net (code "16") (name "AUDIO_OUT_1") (class "Default")
      (node (ref "J_AUDIO_OUT_1") (pin "TIP") (pinfunction "TIP_TIP") (pintype "passive"))
      (node (ref "R67") (pin "2") (pinfunction "2_2") (pintype "passive"))
    )
    (net (code "17") (name "AUDIO_OUT_2") (class "Default")
      (node (ref "J_AUDIO_OUT_2") (pin "TIP") (pinfunction "TIP_TIP") (pintype "passive"))
      (node (ref "R72") (pin "2") (pinfunction "2_2") (pintype "passive"))
    )
    (net (code "18") (name "AUDIO_OUT_3") (class "Default")
      (node (ref "J_AUDIO_OUT_3") (pin "TIP") (pinfunction "TIP_TIP") (pintype "passive"))
      (node (ref "R49") (pin "2") (pinfunction "2_2") (pintype "passive"))
    )
    (net (code "19") (name "AUDIO_OUT_4") (class "Default")
      (node (ref "J_AUDIO_OUT_4") (pin "TIP") (pinfunction "TIP_TIP") (pintype "passive"))
      (node (ref "R51") (pin "2") (pinfunction "2_2") (pintype "passive"))
    )
    (net (code "20") (name "CV_IN_1") (class "Default")
      (node (ref "J_CV_1") (pin "TIP") (pinfunction "TIP_TIP") (pintype "passive"))
      (node (ref "R107") (pin "1") (pinfunction "1_1") (pintype "passive"))
    )
    (net (code "21") (name "CV_IN_2") (class "Default")
      (node (ref "J_CV_2") (pin "TIP") (pinfunction "TIP_TIP") (pintype "passive"))
      (node (ref "R24") (pin "1") (pinfunction "1_1") (pintype "passive"))
    )
    (net (code "22") (name "CV_IN_3") (class "Default")
      (node (ref "J_CV_3") (pin "TIP") (pinfunction "TIP_TIP") (pintype "passive"))
      (node (ref "R27") (pin "1") (pinfunction "1_1") (pintype "passive"))
    )
    (net (code "23") (name "CV_IN_4") (class "Default")
      (node (ref "J_CV_4") (pin "TIP") (pinfunction "TIP_TIP") (pintype "passive"))
      (node (ref "R32") (pin "1") (pinfunction "1_1") (pintype "passive"))
    )
    (net (code "24") (name "DAC1_OUT1") (class "Default")
      (node (ref "R8") (pin "2") (pinfunction "2_2") (pintype "passive"))
      (node (ref "U_DAISY") (pin "30") (pinfunction "GPIO24(DAC1_OUT1)_30") (pintype "bidirectional"))
      (node (ref "U_DAISY") (pin "B30") (pinfunction "GPIO24(DAC1_OUT1)_B30") (pintype "bidirectional"))
    )
    (net (code "25") (name "DAC1_OUT1_") (class "Default")
      (node (ref "J_CV_OUT_1") (pin "TIP") (pinfunction "TIP_TIP") (pintype "passive"))
      (node (ref "R12") (pin "1") (pinfunction "1_1") (pintype "passive"))
    )
    (net (code "26") (name "DAC1_OUT2") (class "Default")
      (node (ref "R10") (pin "2") (pinfunction "2_2") (pintype "passive"))
      (node (ref "U_DAISY") (pin "29") (pinfunction "GPIO23(DAC1_OUT2)_29") (pintype "bidirectional"))
      (node (ref "U_DAISY") (pin "B29") (pinfunction "GPIO23(DAC1_OUT2)_B29") (pintype "bidirectional"))
    )
    (net (code "27") (name "DAC1_OUT2_") (class "Default")
      (node (ref "J_CV_OUT_2") (pin "TIP") (pinfunction "TIP_TIP") (pintype "passive"))
      (node (ref "R13") (pin "1") (pinfunction "1_1") (pintype "passive"))
    )
    (net (code "28") (name "ENC_A") (class "Default")
      (node (ref "ENC_1") (pin "B") (pinfunction "B_B") (pintype "passive"))
      (node (ref "U_DAISY") (pin "13") (pinfunction "GPIO13(I2C1_SDA)_13") (pintype "bidirectional"))
      (node (ref "U_DAISY") (pin "B13") (pinfunction "GPIO13(I2C1_SDA)_B13") (pintype "bidirectional"))
    )
    (net (code "29") (name "ENC_B") (class "Default")
      (node (ref "ENC_1") (pin "A") (pinfunction "A_A") (pintype "passive"))
      (node (ref "U_DAISY") (pin "12") (pinfunction "GPIO12(I2C1_SCL)_12") (pintype "bidirectional"))
      (node (ref "U_DAISY") (pin "B12") (pinfunction "GPIO12(I2C1_SCL)_B12") (pintype "bidirectional"))
    )
    (net (code "30") (name "ENC_CLICK") (class "Default")
      (node (ref "ENC_1") (pin "E") (pinfunction "2_E") (pintype "passive"))
      (node (ref "U_DAISY") (pin "1") (pinfunction "GPIO1(USB_HS_ID)_1") (pintype "bidirectional"))
      (node (ref "U_DAISY") (pin "B1") (pinfunction "GPIO1(USB_HS_ID)_B1") (pintype "bidirectional"))
    )
    (net (code "31") (name "EXT_AUDIO_IN_L") (class "Default")
      (node (ref "C40") (pin "2") (pinfunction "2_2") (pintype "passive"))
      (node (ref "U2") (pin "2") (pinfunction "LIN_2") (pintype "bidirectional"))
    )
    (net (code "32") (name "EXT_AUDIO_IN_R") (class "Default")
      (node (ref "C41") (pin "2") (pinfunction "2_2") (pintype "passive"))
      (node (ref "U2") (pin "1") (pinfunction "RIN_1") (pintype "bidirectional"))
    )
    (net (code "33") (name "EXT_AUDIO_OUT_L") (class "Default")
      (node (ref "C55") (pin "1") (pinfunction "1_1") (pintype "passive"))
      (node (ref "U2") (pin "19") (pinfunction "LOU_19") (pintype "bidirectional"))
    )
    (net (code "34") (name "EXT_AUDIO_OUT_R") (class "Default")
      (node (ref "C56") (pin "1") (pinfunction "1_1") (pintype "passive"))
      (node (ref "U2") (pin "20") (pinfunction "ROU_20") (pintype "bidirectional"))
    )
    (net (code "35") (name "GATE_IN_1") (class "Default")
      (node (ref "R30") (pin "1") (pinfunction "1_1") (pintype "passive"))
      (node (ref "U_DAISY") (pin "27") (pinfunction "GPIO21(ADC1_INP11)_27") (pintype "bidirectional"))
      (node (ref "U_DAISY") (pin "B27") (pinfunction "GPIO21(ADC1_INP11)_B27") (pintype "bidirectional"))
    )
    (net (code "36") (name "GATE_IN_2") (class "Default")
      (node (ref "R37") (pin "1") (pinfunction "1_1") (pintype "passive"))
      (node (ref "U_DAISY") (pin "26") (pinfunction "GPIO20(ADC1_INP3)_26") (pintype "bidirectional"))
      (node (ref "U_DAISY") (pin "B26") (pinfunction "GPIO20(ADC1_INP3)_B26") (pintype "bidirectional"))
    )
    (net (code "37") (name "GATE_OUT") (class "Default")
      (node (ref "R112") (pin "2") (pinfunction "2_2") (pintype "passive"))
      (node (ref "U_DAISY") (pin "24") (pinfunction "GPIO18(ADC1_INP5)_24") (pintype "bidirectional"))
      (node (ref "U_DAISY") (pin "B24") (pinfunction "GPIO18(ADC1_INP5)_B24") (pintype "bidirectional"))
    )
    (net (code "38") (name "GND") (class "Default")
      (node (ref "C1") (pin "2") (pinfunction "2_2") (pintype "passive"))
      (node (ref "C10") (pin "1") (pinfunction "1_1") (pintype "passive"))
      (node (ref "C13") (pin "2") (pinfunction "2_2") (pintype "passive"))
      (node (ref "C14") (pin "2") (pinfunction "2_2") (pintype "passive"))
      (node (ref "C16") (pin "2") (pinfunction "2_2") (pintype "passive"))
      (node (ref "C2") (pin "2") (pinfunction "2_2") (pintype "passive"))
      (node (ref "C20") (pin "2") (pinfunction "2_2") (pintype "passive"))
      (node (ref "C21") (pin "1") (pinfunction "1_1") (pintype "passive"))
      (node (ref "C22") (pin "2") (pinfunction "2_2") (pintype "passive"))
      (node (ref "C23") (pin "1") (pinfunction "1_1") (pintype "passive"))
      (node (ref "C29") (pin "2") (pinfunction "2_2") (pintype "passive"))
      (node (ref "C3") (pin "2") (pinfunction "2_2") (pintype "passive"))
      (node (ref "C30") (pin "1") (pinfunction "1_1") (pintype "passive"))
      (node (ref "C34") (pin "2") (pinfunction "2_2") (pintype "passive"))
      (node (ref "C35") (pin "1") (pinfunction "1_1") (pintype "passive"))
      (node (ref "C36") (pin "2") (pinfunction "2_2") (pintype "passive"))
      (node (ref "C37") (pin "1") (pinfunction "1_1") (pintype "passive"))
      (node (ref "C39") (pin "1") (pinfunction "1_1") (pintype "passive"))
      (node (ref "C4") (pin "2") (pinfunction "2_2") (pintype "passive"))
      (node (ref "C42") (pin "-") (pinfunction "NEG_-") (pintype "passive"))
      (node (ref "C43") (pin "1") (pinfunction "1_1") (pintype "passive"))
      (node (ref "C44") (pin "2") (pinfunction "2_2") (pintype "passive"))
      (node (ref "C45") (pin "1") (pinfunction "1_1") (pintype "passive"))
      (node (ref "C5") (pin "1") (pinfunction "1_1") (pintype "passive"))
      (node (ref "C50") (pin "2") (pinfunction "2_2") (pintype "passive"))
      (node (ref "C51") (pin "1") (pinfunction "1_1") (pintype "passive"))
      (node (ref "C8") (pin "1") (pinfunction "1_1") (pintype "passive"))
      (node (ref "C9") (pin "2") (pinfunction "2_2") (pintype "passive"))
      (node (ref "ENC_1") (pin "C") (pinfunction "C_C") (pintype "passive"))
      (node (ref "ENC_1") (pin "D") (pinfunction "1_D") (pintype "passive"))
      (node (ref "EP1") (pin "GND1A") (pinfunction "GND_GND1A") (pintype "bidirectional"))
      (node (ref "EP1") (pin "GND1B") (pinfunction "GND_GND1B") (pintype "bidirectional"))
      (node (ref "EP1") (pin "GND2A") (pinfunction "GND_GND2A") (pintype "bidirectional"))
      (node (ref "EP1") (pin "GND2B") (pinfunction "GND_GND2B") (pintype "bidirectional"))
      (node (ref "EP1") (pin "GND3A") (pinfunction "GND_GND3A") (pintype "bidirectional"))
      (node (ref "EP1") (pin "GND3B") (pinfunction "GND_GND3B") (pintype "bidirectional"))
      (node (ref "J_AUDIO_IN_1") (pin "GND") (pinfunction "GND_GND") (pintype "passive"))
      (node (ref "J_AUDIO_IN_2") (pin "GND") (pinfunction "GND_GND") (pintype "passive"))
      (node (ref "J_AUDIO_IN_3") (pin "GND") (pinfunction "GND_GND") (pintype "passive"))
      (node (ref "J_AUDIO_IN_4") (pin "GND") (pinfunction "GND_GND") (pintype "passive"))
      (node (ref "J_AUDIO_OUT_1") (pin "GND") (pinfunction "GND_GND") (pintype "passive"))
      (node (ref "J_AUDIO_OUT_2") (pin "GND") (pinfunction "GND_GND") (pintype "passive"))
      (node (ref "J_AUDIO_OUT_3") (pin "GND") (pinfunction "GND_GND") (pintype "passive"))
      (node (ref "J_AUDIO_OUT_4") (pin "GND") (pinfunction "GND_GND") (pintype "passive"))
      (node (ref "J_CV_1") (pin "GND") (pinfunction "GND_GND") (pintype "passive"))
      (node (ref "J_CV_2") (pin "GND") (pinfunction "GND_GND") (pintype "passive"))
      (node (ref "J_CV_3") (pin "GND") (pinfunction "GND_GND") (pintype "passive"))
      (node (ref "J_CV_4") (pin "GND") (pinfunction "GND_GND") (pintype "passive"))
      (node (ref "J_CV_OUT_1") (pin "GND") (pinfunction "GND_GND") (pintype "passive"))
      (node (ref "J_CV_OUT_2") (pin "GND") (pinfunction "GND_GND") (pintype "passive"))
      (node (ref "J_GATE_IN_1") (pin "GND") (pinfunction "GND_GND") (pintype "passive"))
      (node (ref "J_GATE_IN_2") (pin "GND") (pinfunction "GND_GND") (pintype "passive"))
      (node (ref "J_GATE_OUT") (pin "GND") (pinfunction "GND_GND") (pintype "passive"))
      (node (ref "J_MIDI_IN") (pin "GND") (pinfunction "GND_GND") (pintype "passive"))
      (node (ref "J_MIDI_OUT") (pin "GND") (pinfunction "GND_GND") (pintype "passive"))
      (node (ref "Q1") (pin "E") (pinfunction "E_E") (pintype "passive"))
      (node (ref "Q2") (pin "E") (pinfunction "E_E") (pintype "passive"))
      (node (ref "R28") (pin "1") (pinfunction "1_1") (pintype "passive"))
      (node (ref "R35") (pin "1") (pinfunction "1_1") (pintype "passive"))
      (node (ref "R85") (pin "1") (pinfunction "1_1") (pintype "passive"))
      (node (ref "R86") (pin "1") (pinfunction "1_1") (pintype "passive"))
      (node (ref "U$1") (pin "P$4") (pinfunction "OUT-_P$4") (pintype "bidirectional"))
      (node (ref "U11") (pin "10") (pinfunction "+IN_10") (pintype "input"))
      (node (ref "U11") (pin "12") (pinfunction "+IN_12") (pintype "input"))
      (node (ref "U11") (pin "3") (pinfunction "+IN_3") (pintype "input"))
      (node (ref "U11") (pin "5") (pinfunction "+IN_5") (pintype "input"))
      (node (ref "U13") (pin "10") (pinfunction "+IN_10") (pintype "input"))
      (node (ref "U13") (pin "12") (pinfunction "+IN_12") (pintype "input"))
      (node (ref "U13") (pin "3") (pinfunction "+IN_3") (pintype "input"))
      (node (ref "U13") (pin "5") (pinfunction "+IN_5") (pintype "input"))
      (node (ref "U14") (pin "10") (pinfunction "+IN_10") (pintype "input"))
      (node (ref "U14") (pin "12") (pinfunction "+IN_12") (pintype "input"))
      (node (ref "U14") (pin "3") (pinfunction "+IN_3") (pintype "input"))
      (node (ref "U14") (pin "5") (pinfunction "+IN_5") (pintype "input"))
      (node (ref "U15") (pin "5") (pinfunction "GND_5") (pintype "bidirectional"))
      (node (ref "U16") (pin "10") (pinfunction "+IN_10") (pintype "input"))
      (node (ref "U16") (pin "12") (pinfunction "+IN_12") (pintype "input"))
      (node (ref "U16") (pin "3") (pinfunction "+IN_3") (pintype "input"))
      (node (ref "U16") (pin "5") (pinfunction "+IN_5") (pintype "input"))
      (node (ref "U2") (pin "10") (pinfunction "CSK1_10") (pintype "bidirectional"))
      (node (ref "U2") (pin "11") (pinfunction "CSK2_11") (pintype "bidirectional"))
      (node (ref "U2") (pin "3") (pinfunction "GND_3") (pintype "bidirectional"))
      (node (ref "U2") (pin "7") (pinfunction "DEM1_7") (pintype "bidirectional"))
      (node (ref "U2") (pin "9") (pinfunction "CSK0_9") (pintype "bidirectional"))
      (node (ref "U3") (pin "GND1") (pinfunction "SHIELD_GND1") (pintype "bidirectional"))
      (node (ref "U3") (pin "GND2") (pinfunction "SHIELD_GND2") (pintype "bidirectional"))
      (node (ref "U3") (pin "P$6") (pinfunction "GND_P$6") (pintype "bidirectional"))
      (node (ref "U4") (pin "10") (pinfunction "+IN_10") (pintype "input"))
      (node (ref "U4") (pin "12") (pinfunction "+IN_12") (pintype "input"))
      (node (ref "U4") (pin "3") (pinfunction "+IN_3") (pintype "input"))
      (node (ref "U4") (pin "5") (pinfunction "+IN_5") (pintype "input"))
      (node (ref "U5") (pin "10") (pinfunction "+IN_10") (pintype "input"))
      (node (ref "U5") (pin "12") (pinfunction "+IN_12") (pintype "input"))
      (node (ref "U5") (pin "3") (pinfunction "+IN_3") (pintype "input"))
      (node (ref "U5") (pin "5") (pinfunction "+IN_5") (pintype "input"))
      (node (ref "U6") (pin "1") (pinfunction "C_1") (pintype "passive"))
      (node (ref "U7") (pin "10") (pinfunction "+IN_10") (pintype "input"))
      (node (ref "U7") (pin "11") (pinfunction "V-_11") (pintype "power_in"))
      (node (ref "U7") (pin "12") (pinfunction "+IN_12") (pintype "input"))
      (node (ref "U7") (pin "3") (pinfunction "+IN_3") (pintype "input"))
      (node (ref "U7") (pin "5") (pinfunction "+IN_5") (pintype "input"))
      (node (ref "U_DAISY") (pin "20") (pinfunction "AGND_20") (pintype "bidirectional"))
      (node (ref "U_DAISY") (pin "40") (pinfunction "GND_40") (pintype "bidirectional"))
      (node (ref "U_DAISY") (pin "B20") (pinfunction "AGND_B20") (pintype "bidirectional"))
      (node (ref "U_DAISY") (pin "B40") (pinfunction "GND_B40") (pintype "bidirectional"))
      (node (ref "U_OLED") (pin "1") (pinfunction "GND_1") (pintype "bidirectional"))
      (node (ref "VR_1") (pin "1") (pinfunction "1_1") (pintype "passive"))
      (node (ref "VR_2") (pin "1") (pinfunction "1_1") (pintype "passive"))
      (node (ref "VR_3") (pin "1") (pinfunction "1_1") (pintype "passive"))
      (node (ref "VR_4") (pin "1") (pinfunction "1_1") (pintype "passive"))
    )
    (net (code "39") (name "INT_AUDIO_IN_L") (class "Default")
      (node (ref "R82") (pin "2") (pinfunction "2_2") (pintype "passive"))
      (node (ref "U_DAISY") (pin "16") (pinfunction "AUDIO_IN_L_16") (pintype "bidirectional"))
      (node (ref "U_DAISY") (pin "B16") (pinfunction "AUDIO_IN_L_B16") (pintype "bidirectional"))
    )
    (net (code "40") (name "INT_AUDIO_IN_R") (class "Default")
      (node (ref "R98") (pin "2") (pinfunction "2_2") (pintype "passive"))
      (node (ref "U_DAISY") (pin "17") (pinfunction "AUDIO_IN_R_17") (pintype "bidirectional"))
      (node (ref "U_DAISY") (pin "B17") (pinfunction "AUDIO_IN_R_B17") (pintype "bidirectional"))
    )
    (net (code "41") (name "INT_AUDIO_OUT_L") (class "Default")
      (node (ref "R102") (pin "1") (pinfunction "1_1") (pintype "passive"))
      (node (ref "U_DAISY") (pin "18") (pinfunction "AUDIO_OUT_L_18") (pintype "bidirectional"))
      (node (ref "U_DAISY") (pin "B18") (pinfunction "AUDIO_OUT_L_B18") (pintype "bidirectional"))
    )
    (net (code "42") (name "INT_AUDIO_OUT_R") (class "Default")
      (node (ref "R104") (pin "1") (pinfunction "1_1") (pintype "passive"))
      (node (ref "U_DAISY") (pin "19") (pinfunction "AUDIO_OUT_R_19") (pintype "bidirectional"))
      (node (ref "U_DAISY") (pin "B19") (pinfunction "AUDIO_OUT_R_B19") (pintype "bidirectional"))
    )
    (net (code "43") (name "KNOB_1") (class "Default")
      (node (ref "R108") (pin "1") (pinfunction "1_1") (pintype "passive"))
      (node (ref "VR_1") (pin "2") (pinfunction "2_2") (pintype "passive"))
    )
    (net (code "44") (name "KNOB_2") (class "Default")
      (node (ref "R109") (pin "1") (pinfunction "1_1") (pintype "passive"))
      (node (ref "VR_2") (pin "2") (pinfunction "2_2") (pintype "passive"))
    )
    (net (code "45") (name "KNOB_3") (class "Default")
      (node (ref "R110") (pin "1") (pinfunction "1_1") (pintype "passive"))
      (node (ref "VR_3") (pin "2") (pinfunction "2_2") (pintype "passive"))
    )
    (net (code "46") (name "KNOB_4") (class "Default")
      (node (ref "R111") (pin "1") (pinfunction "1_1") (pintype "passive"))
      (node (ref "VR_4") (pin "2") (pinfunction "2_2") (pintype "passive"))
    )
    (net (code "47") (name "MIDI_IN_A") (class "Default")
      (node (ref "R63") (pin "2") (pinfunction "2_2") (pintype "passive"))
      (node (ref "R78") (pin "1") (pinfunction "1_1") (pintype "passive"))
      (node (ref "R79") (pin "1") (pinfunction "1_1") (pintype "passive"))
    )
    (net (code "48") (name "MIDI_IN_B") (class "Default")
      (node (ref "D5") (pin "A") (pinfunction "A_A") (pintype "passive"))
      (node (ref "R83") (pin "1") (pinfunction "1_1") (pintype "passive"))
      (node (ref "R84") (pin "1") (pinfunction "1_1") (pintype "passive"))
      (node (ref "U15") (pin "2") (pinfunction "C_2") (pintype "bidirectional"))
    )
    (net (code "49") (name "MIDI_IN_RING") (class "Default")
      (node (ref "J_MIDI_IN") (pin "RING") (pinfunction "NORM_RING") (pintype "passive"))
      (node (ref "R79") (pin "2") (pinfunction "2_2") (pintype "passive"))
      (node (ref "R84") (pin "2") (pinfunction "2_2") (pintype "passive"))
    )
    (net (code "50") (name "MIDI_IN_TIP") (class "Default")
      (node (ref "J_MIDI_IN") (pin "TIP") (pinfunction "TIP_TIP") (pintype "passive"))
      (node (ref "R78") (pin "2") (pinfunction "2_2") (pintype "passive"))
      (node (ref "R83") (pin "2") (pinfunction "2_2") (pintype "passive"))
    )
    (net (code "51") (name "Net-(C33-NEG)") (class "Default")
      (node (ref "C31") (pin "1") (pinfunction "1_1") (pintype "passive"))
      (node (ref "C33") (pin "-") (pinfunction "NEG_-") (pintype "passive"))
      (node (ref "R68") (pin "1") (pinfunction "1_1") (pintype "passive"))
      (node (ref "R69") (pin "1") (pinfunction "1_1") (pintype "passive"))
      (node (ref "R76") (pin "2") (pinfunction "2_2") (pintype "passive"))
      (node (ref "R77") (pin "2") (pinfunction "2_2") (pintype "passive"))
    )
    (net (code "52") (name "Net-(C33-POS)") (class "Default")
      (node (ref "C31") (pin "2") (pinfunction "2_2") (pintype "passive"))
      (node (ref "C33") (pin "+") (pinfunction "POS_+") (pintype "passive"))
      (node (ref "R62") (pin "1") (pinfunction "1_1") (pintype "passive"))
      (node (ref "R65") (pin "1") (pinfunction "1_1") (pintype "passive"))
      (node (ref "R70") (pin "2") (pinfunction "2_2") (pintype "passive"))
      (node (ref "R75") (pin "2") (pinfunction "2_2") (pintype "passive"))
    )
    (net (code "53") (name "Net-(C38-NEG)") (class "Default")
      (node (ref "C32") (pin "1") (pinfunction "1_1") (pintype "passive"))
      (node (ref "C38") (pin "-") (pinfunction "NEG_-") (pintype "passive"))
      (node (ref "L2") (pin "P$1") (pinfunction "P$1_P$1") (pintype "bidirectional"))
      (node (ref "R68") (pin "2") (pinfunction "2_2") (pintype "passive"))
      (node (ref "R69") (pin "2") (pinfunction "2_2") (pintype "passive"))
    )
    (net (code "54") (name "Net-(C38-POS)") (class "Default")
      (node (ref "C32") (pin "2") (pinfunction "2_2") (pintype "passive"))
      (node (ref "C38") (pin "+") (pinfunction "POS_+") (pintype "passive"))
      (node (ref "L1") (pin "P$1") (pinfunction "P$1_P$1") (pintype "bidirectional"))
      (node (ref "R62") (pin "2") (pinfunction "2_2") (pintype "passive"))
      (node (ref "R65") (pin "2") (pinfunction "2_2") (pintype "passive"))
    )
    (net (code "55") (name "Net-(C40-Pad1)") (class "Default")
      (node (ref "C40") (pin "1") (pinfunction "1_1") (pintype "passive"))
      (node (ref "R46") (pin "2") (pinfunction "2_2") (pintype "passive"))
    )
    (net (code "56") (name "Net-(C41-Pad1)") (class "Default")
      (node (ref "C41") (pin "1") (pinfunction "1_1") (pintype "passive"))
      (node (ref "R47") (pin "2") (pinfunction "2_2") (pintype "passive"))
    )
    (net (code "57") (name "Net-(C55-Pad2)") (class "Default")
      (node (ref "C55") (pin "2") (pinfunction "2_2") (pintype "passive"))
      (node (ref "R57") (pin "1") (pinfunction "1_1") (pintype "passive"))
      (node (ref "R85") (pin "2") (pinfunction "2_2") (pintype "passive"))
    )
    (net (code "58") (name "Net-(C56-Pad2)") (class "Default")
      (node (ref "C56") (pin "2") (pinfunction "2_2") (pintype "passive"))
      (node (ref "R59") (pin "1") (pinfunction "1_1") (pintype "passive"))
      (node (ref "R86") (pin "2") (pinfunction "2_2") (pintype "passive"))
    )
    (net (code "59") (name "Net-(D1-PadA)") (class "Default")
      (node (ref "D1") (pin "A") (pinfunction "A_A") (pintype "passive"))
      (node (ref "FB2") (pin "2") (pinfunction "2_2") (pintype "passive"))
    )
    (net (code "60") (name "Net-(D2-PadC)") (class "Default")
      (node (ref "D2") (pin "C") (pinfunction "C_C") (pintype "passive"))
      (node (ref "FB3") (pin "2") (pinfunction "2_2") (pintype "passive"))
    )
    (net (code "61") (name "Net-(EP1-+12VIN-PadP12VA)") (class "Default")
      (node (ref "EP1") (pin "P12VA") (pinfunction "+12VIN_P12VA") (pintype "bidirectional"))
      (node (ref "EP1") (pin "P12VB") (pinfunction "+12VIN_P12VB") (pintype "bidirectional"))
      (node (ref "FB2") (pin "1") (pinfunction "1_1") (pintype "passive"))
    )
    (net (code "62") (name "Net-(EP1--12VIN-PadN12VA)") (class "Default")
      (node (ref "EP1") (pin "N12VA") (pinfunction "-12VIN_N12VA") (pintype "bidirectional"))
      (node (ref "EP1") (pin "N12VB") (pinfunction "-12VIN_N12VB") (pintype "bidirectional"))
      (node (ref "FB3") (pin "1") (pinfunction "1_1") (pintype "passive"))
    )
    (net (code "63") (name "Net-(J_GATE_IN_2-PadTIP)") (class "Default")
      (node (ref "J_GATE_IN_2") (pin "TIP") (pinfunction "TIP_TIP") (pintype "passive"))
      (node (ref "R34") (pin "1") (pinfunction "1_1") (pintype "passive"))
    )
    (net (code "64") (name "Net-(J_MIDI_OUT-NORM)") (class "Default")
      (node (ref "J_MIDI_OUT") (pin "RING") (pinfunction "NORM_RING") (pintype "passive"))
      (node (ref "R1") (pin "2") (pinfunction "2_2") (pintype "passive"))
    )
    (net (code "65") (name "Net-(J_MIDI_OUT-PadTIP)") (class "Default")
      (node (ref "J_MIDI_OUT") (pin "TIP") (pinfunction "TIP_TIP") (pintype "passive"))
      (node (ref "R2") (pin "1") (pinfunction "1_1") (pintype "passive"))
    )
    (net (code "66") (name "Net-(Q1-PadB)") (class "Default")
      (node (ref "Q1") (pin "B") (pinfunction "B_B") (pintype "passive"))
      (node (ref "R21") (pin "2") (pinfunction "2_2") (pintype "passive"))
      (node (ref "R28") (pin "2") (pinfunction "2_2") (pintype "passive"))
    )
    (net (code "67") (name "Net-(Q1-PadC)") (class "Default")
      (node (ref "Q1") (pin "C") (pinfunction "C_C") (pintype "passive"))
      (node (ref "R29") (pin "1") (pinfunction "1_1") (pintype "passive"))
      (node (ref "R30") (pin "2") (pinfunction "2_2") (pintype "passive"))
    )
    (net (code "68") (name "Net-(Q2-PadB)") (class "Default")
      (node (ref "Q2") (pin "B") (pinfunction "B_B") (pintype "passive"))
      (node (ref "R34") (pin "2") (pinfunction "2_2") (pintype "passive"))
      (node (ref "R35") (pin "2") (pinfunction "2_2") (pintype "passive"))
    )
    (net (code "69") (name "Net-(Q2-PadC)") (class "Default")
      (node (ref "Q2") (pin "C") (pinfunction "C_C") (pintype "passive"))
      (node (ref "R36") (pin "1") (pinfunction "1_1") (pintype "passive"))
      (node (ref "R37") (pin "2") (pinfunction "2_2") (pintype "passive"))
    )
    (net (code "70") (name "Net-(U$1-IN+)") (class "Default")
      (node (ref "L1") (pin "P$2") (pinfunction "P$2_P$2") (pintype "bidirectional"))
      (node (ref "U$1") (pin "P$2") (pinfunction "IN+_P$2") (pintype "bidirectional"))
    )
    (net (code "71") (name "Net-(U$1-IN-)") (class "Default")
      (node (ref "L2") (pin "P$2") (pinfunction "P$2_P$2") (pintype "bidirectional"))
      (node (ref "U$1") (pin "P$1") (pinfunction "IN-_P$1") (pintype "bidirectional"))
    )
    (net (code "72") (name "Net-(U$1-OUT+)") (class "Default")
      (node (ref "C39") (pin "2") (pinfunction "2_2") (pintype "passive"))
      (node (ref "FB1") (pin "1") (pinfunction "1_1") (pintype "passive"))
      (node (ref "U$1") (pin "P$5") (pinfunction "OUT+_P$5") (pintype "bidirectional"))
    )
    (net (code "73") (name "Net-(U2C-VCOM)") (class "Default")
      (node (ref "C5") (pin "2") (pinfunction "2_2") (pintype "passive"))
      (node (ref "C8") (pin "2") (pinfunction "2_2") (pintype "passive"))
      (node (ref "U2") (pin "18") (pinfunction "VCOM_18") (pintype "bidirectional"))
    )
    (net (code "74") (name "Net-(U2C-VD)") (class "Default")
      (node (ref "C2") (pin "1") (pinfunction "1_1") (pintype "passive"))
      (node (ref "C3") (pin "1") (pinfunction "1_1") (pintype "passive"))
      (node (ref "R19") (pin "2") (pinfunction "2_2") (pintype "passive"))
      (node (ref "U2") (pin "5") (pinfunction "VD_5") (pintype "bidirectional"))
    )
    (net (code "75") (name "Net-(U4A--IN)") (class "Default")
      (node (ref "C46") (pin "1") (pinfunction "1_1") (pintype "passive"))
      (node (ref "R55") (pin "2") (pinfunction "2_2") (pintype "passive"))
      (node (ref "R56") (pin "1") (pinfunction "1_1") (pintype "passive"))
      (node (ref "U4") (pin "2") (pinfunction "-IN_2") (pintype "input"))
    )
    (net (code "76") (name "Net-(U4A-OUT)") (class "Default")
      (node (ref "C46") (pin "2") (pinfunction "2_2") (pintype "passive"))
      (node (ref "R56") (pin "2") (pinfunction "2_2") (pintype "passive"))
      (node (ref "R73") (pin "1") (pinfunction "1_1") (pintype "passive"))
      (node (ref "U4") (pin "1") (pinfunction "OUT_1") (pintype "output"))
    )
    (net (code "77") (name "Net-(U4B--IN)") (class "Default")
      (node (ref "C47") (pin "1") (pinfunction "1_1") (pintype "passive"))
      (node (ref "R60") (pin "2") (pinfunction "2_2") (pintype "passive"))
      (node (ref "R61") (pin "1") (pinfunction "1_1") (pintype "passive"))
      (node (ref "U4") (pin "6") (pinfunction "-IN_6") (pintype "input"))
    )
    (net (code "78") (name "Net-(U4B-OUT)") (class "Default")
      (node (ref "C47") (pin "2") (pinfunction "2_2") (pintype "passive"))
      (node (ref "R61") (pin "2") (pinfunction "2_2") (pintype "passive"))
      (node (ref "R80") (pin "1") (pinfunction "1_1") (pintype "passive"))
      (node (ref "U4") (pin "7") (pinfunction "OUT_7") (pintype "output"))
    )
    (net (code "79") (name "Net-(U4C--IN)") (class "Default")
      (node (ref "C49") (pin "1") (pinfunction "1_1") (pintype "passive"))
      (node (ref "R80") (pin "2") (pinfunction "2_2") (pintype "passive"))
      (node (ref "R81") (pin "1") (pinfunction "1_1") (pintype "passive"))
      (node (ref "U4") (pin "9") (pinfunction "-IN_9") (pintype "input"))
    )
    (net (code "80") (name "Net-(U4C-OUT)") (class "Default")
      (node (ref "C49") (pin "2") (pinfunction "2_2") (pintype "passive"))
      (node (ref "R81") (pin "2") (pinfunction "2_2") (pintype "passive"))
      (node (ref "R98") (pin "1") (pinfunction "1_1") (pintype "passive"))
      (node (ref "U4") (pin "8") (pinfunction "OUT_8") (pintype "output"))
    )
    (net (code "81") (name "Net-(U4D--IN)") (class "Default")
      (node (ref "C48") (pin "1") (pinfunction "1_1") (pintype "passive"))
      (node (ref "R73") (pin "2") (pinfunction "2_2") (pintype "passive"))
      (node (ref "R74") (pin "1") (pinfunction "1_1") (pintype "passive"))
      (node (ref "U4") (pin "13") (pinfunction "-IN_13") (pintype "input"))
    )
    (net (code "82") (name "Net-(U4D-OUT)") (class "Default")
      (node (ref "C48") (pin "2") (pinfunction "2_2") (pintype "passive"))
      (node (ref "R74") (pin "2") (pinfunction "2_2") (pintype "passive"))
      (node (ref "R82") (pin "1") (pinfunction "1_1") (pintype "passive"))
      (node (ref "U4") (pin "14") (pinfunction "OUT_14") (pintype "output"))
    )
    (net (code "83") (name "Net-(U5A--IN)") (class "Default")
      (node (ref "R10") (pin "1") (pinfunction "1_1") (pintype "passive"))
      (node (ref "R11") (pin "2") (pinfunction "2_2") (pintype "passive"))
      (node (ref "U5") (pin "2") (pinfunction "-IN_2") (pintype "input"))
    )
    (net (code "84") (name "Net-(U5A-OUT)") (class "Default")
      (node (ref "R11") (pin "1") (pinfunction "1_1") (pintype "passive"))
      (node (ref "R16") (pin "2") (pinfunction "2_2") (pintype "passive"))
      (node (ref "U5") (pin "1") (pinfunction "OUT_1") (pintype "output"))
    )
    (net (code "85") (name "Net-(U5B--IN)") (class "Default")
      (node (ref "R8") (pin "1") (pinfunction "1_1") (pintype "passive"))
      (node (ref "R9") (pin "2") (pinfunction "2_2") (pintype "passive"))
      (node (ref "U5") (pin "6") (pinfunction "-IN_6") (pintype "input"))
    )
    (net (code "86") (name "Net-(U5B-OUT)") (class "Default")
      (node (ref "R14") (pin "2") (pinfunction "2_2") (pintype "passive"))
      (node (ref "R9") (pin "1") (pinfunction "1_1") (pintype "passive"))
      (node (ref "U5") (pin "7") (pinfunction "OUT_7") (pintype "output"))
    )
    (net (code "87") (name "Net-(U5C--IN)") (class "Default")
      (node (ref "R14") (pin "1") (pinfunction "1_1") (pintype "passive"))
      (node (ref "R15") (pin "2") (pinfunction "2_2") (pintype "passive"))
      (node (ref "U5") (pin "9") (pinfunction "-IN_9") (pintype "input"))
    )
    (net (code "88") (name "Net-(U5C-OUT)") (class "Default")
      (node (ref "R12") (pin "2") (pinfunction "2_2") (pintype "passive"))
      (node (ref "R15") (pin "1") (pinfunction "1_1") (pintype "passive"))
      (node (ref "U5") (pin "8") (pinfunction "OUT_8") (pintype "output"))
    )
    (net (code "89") (name "Net-(U5D--IN)") (class "Default")
      (node (ref "R16") (pin "1") (pinfunction "1_1") (pintype "passive"))
      (node (ref "R17") (pin "2") (pinfunction "2_2") (pintype "passive"))
      (node (ref "U5") (pin "13") (pinfunction "-IN_13") (pintype "input"))
    )
    (net (code "90") (name "Net-(U5D-OUT)") (class "Default")
      (node (ref "R13") (pin "2") (pinfunction "2_2") (pintype "passive"))
      (node (ref "R17") (pin "1") (pinfunction "1_1") (pintype "passive"))
      (node (ref "U5") (pin "14") (pinfunction "OUT_14") (pintype "output"))
    )
    (net (code "91") (name "Net-(U7A--IN)") (class "Default")
      (node (ref "C12") (pin "1") (pinfunction "1_1") (pintype "passive"))
      (node (ref "R110") (pin "2") (pinfunction "2_2") (pintype "passive"))
      (node (ref "R25") (pin "1") (pinfunction "1_1") (pintype "passive"))
      (node (ref "R26") (pin "2") (pinfunction "2_2") (pintype "passive"))
      (node (ref "R27") (pin "2") (pinfunction "2_2") (pintype "passive"))
      (node (ref "U7") (pin "2") (pinfunction "-IN_2") (pintype "input"))
    )
    (net (code "92") (name "Net-(U7B--IN)") (class "Default")
      (node (ref "C11") (pin "1") (pinfunction "1_1") (pintype "passive"))
      (node (ref "R109") (pin "2") (pinfunction "2_2") (pintype "passive"))
      (node (ref "R22") (pin "1") (pinfunction "1_1") (pintype "passive"))
      (node (ref "R23") (pin "2") (pinfunction "2_2") (pintype "passive"))
      (node (ref "R24") (pin "2") (pinfunction "2_2") (pintype "passive"))
      (node (ref "U7") (pin "6") (pinfunction "-IN_6") (pintype "input"))
    )
    (net (code "93") (name "Net-(U7C--IN)") (class "Default")
      (node (ref "C54") (pin "1") (pinfunction "1_1") (pintype "passive"))
      (node (ref "R105") (pin "1") (pinfunction "1_1") (pintype "passive"))
      (node (ref "R106") (pin "2") (pinfunction "2_2") (pintype "passive"))
      (node (ref "R107") (pin "2") (pinfunction "2_2") (pintype "passive"))
      (node (ref "R108") (pin "2") (pinfunction "2_2") (pintype "passive"))
      (node (ref "U7") (pin "9") (pinfunction "-IN_9") (pintype "input"))
    )
    (net (code "94") (name "Net-(U7D--IN)") (class "Default")
      (node (ref "C15") (pin "1") (pinfunction "1_1") (pintype "passive"))
      (node (ref "R111") (pin "2") (pinfunction "2_2") (pintype "passive"))
      (node (ref "R31") (pin "2") (pinfunction "2_2") (pintype "passive"))
      (node (ref "R32") (pin "2") (pinfunction "2_2") (pintype "passive"))
      (node (ref "R33") (pin "1") (pinfunction "1_1") (pintype "passive"))
      (node (ref "U7") (pin "13") (pinfunction "-IN_13") (pintype "input"))
    )
    (net (code "95") (name "Net-(U11A--IN)") (class "Default")
      (node (ref "C52") (pin "1") (pinfunction "1_1") (pintype "passive"))
      (node (ref "R102") (pin "2") (pinfunction "2_2") (pintype "passive"))
      (node (ref "R99") (pin "1") (pinfunction "1_1") (pintype "passive"))
      (node (ref "U11") (pin "2") (pinfunction "-IN_2") (pintype "input"))
    )
    (net (code "96") (name "Net-(U11A-OUT)") (class "Default")
      (node (ref "C52") (pin "2") (pinfunction "2_2") (pintype "passive"))
      (node (ref "R101") (pin "1") (pinfunction "1_1") (pintype "passive"))
      (node (ref "R99") (pin "2") (pinfunction "2_2") (pintype "passive"))
      (node (ref "U11") (pin "1") (pinfunction "OUT_1") (pintype "output"))
    )
    (net (code "97") (name "Net-(U11B--IN)") (class "Default")
      (node (ref "C53") (pin "1") (pinfunction "1_1") (pintype "passive"))
      (node (ref "R100") (pin "1") (pinfunction "1_1") (pintype "passive"))
      (node (ref "R104") (pin "2") (pinfunction "2_2") (pintype "passive"))
      (node (ref "U11") (pin "6") (pinfunction "-IN_6") (pintype "input"))
    )
    (net (code "98") (name "Net-(U11B-OUT)") (class "Default")
      (node (ref "C53") (pin "2") (pinfunction "2_2") (pintype "passive"))
      (node (ref "R100") (pin "2") (pinfunction "2_2") (pintype "passive"))
      (node (ref "R103") (pin "1") (pinfunction "1_1") (pintype "passive"))
      (node (ref "U11") (pin "7") (pinfunction "OUT_7") (pintype "output"))
    )
    (net (code "99") (name "Net-(U11C--IN)") (class "Default")
      (node (ref "C26") (pin "1") (pinfunction "1_1") (pintype "passive"))
      (node (ref "R103") (pin "2") (pinfunction "2_2") (pintype "passive"))
      (node (ref "R71") (pin "1") (pinfunction "1_1") (pintype "passive"))
      (node (ref "U11") (pin "9") (pinfunction "-IN_9") (pintype "input"))
    )
    (net (code "100") (name "Net-(U11C-OUT)") (class "Default")
      (node (ref "C26") (pin "2") (pinfunction "2_2") (pintype "passive"))
      (node (ref "R71") (pin "2") (pinfunction "2_2") (pintype "passive"))
      (node (ref "R72") (pin "1") (pinfunction "1_1") (pintype "passive"))
      (node (ref "U11") (pin "8") (pinfunction "OUT_8") (pintype "output"))
    )
    (net (code "101") (name "Net-(U11D--IN)") (class "Default")
      (node (ref "C27") (pin "1") (pinfunction "1_1") (pintype "passive"))
      (node (ref "R101") (pin "2") (pinfunction "2_2") (pintype "passive"))
      (node (ref "R66") (pin "1") (pinfunction "1_1") (pintype "passive"))
      (node (ref "U11") (pin "13") (pinfunction "-IN_13") (pintype "input"))
    )
    (net (code "102") (name "Net-(U11D-OUT)") (class "Default")
      (node (ref "C27") (pin "2") (pinfunction "2_2") (pintype "passive"))
      (node (ref "R66") (pin "2") (pinfunction "2_2") (pintype "passive"))
      (node (ref "R67") (pin "1") (pinfunction "1_1") (pintype "passive"))
      (node (ref "U11") (pin "14") (pinfunction "OUT_14") (pintype "output"))
    )
    (net (code "103") (name "Net-(U13A--IN)") (class "Default")
      (node (ref "U13") (pin "1") (pinfunction "OUT_1") (pintype "output"))
      (node (ref "U13") (pin "2") (pinfunction "-IN_2") (pintype "input"))
    )
    (net (code "104") (name "Net-(U13B--IN)") (class "Default")
      (node (ref "R112") (pin "1") (pinfunction "1_1") (pintype "passive"))
      (node (ref "R113") (pin "2") (pinfunction "2_2") (pintype "passive"))
      (node (ref "U13") (pin "6") (pinfunction "-IN_6") (pintype "input"))
    )
    (net (code "105") (name "Net-(U13B-OUT)") (class "Default")
      (node (ref "R113") (pin "1") (pinfunction "1_1") (pintype "passive"))
      (node (ref "R114") (pin "2") (pinfunction "2_2") (pintype "passive"))
      (node (ref "U13") (pin "7") (pinfunction "OUT_7") (pintype "output"))
    )
    (net (code "106") (name "Net-(U13C--IN)") (class "Default")
      (node (ref "R114") (pin "1") (pinfunction "1_1") (pintype "passive"))
      (node (ref "R115") (pin "2") (pinfunction "2_2") (pintype "passive"))
      (node (ref "U13") (pin "9") (pinfunction "-IN_9") (pintype "input"))
    )
    (net (code "107") (name "Net-(U13C-OUT)") (class "Default")
      (node (ref "R115") (pin "1") (pinfunction "1_1") (pintype "passive"))
      (node (ref "R38") (pin "2") (pinfunction "2_2") (pintype "passive"))
      (node (ref "U13") (pin "8") (pinfunction "OUT_8") (pintype "output"))
    )
    (net (code "108") (name "Net-(U13D--IN)") (class "Default")
      (node (ref "U13") (pin "13") (pinfunction "-IN_13") (pintype "input"))
      (node (ref "U13") (pin "14") (pinfunction "OUT_14") (pintype "output"))
    )
    (net (code "109") (name "Net-(U14A--IN)") (class "Default")
      (node (ref "C6") (pin "1") (pinfunction "1_1") (pintype "passive"))
      (node (ref "R20") (pin "2") (pinfunction "2_2") (pintype "passive"))
      (node (ref "R39") (pin "1") (pinfunction "1_1") (pintype "passive"))
      (node (ref "U14") (pin "2") (pinfunction "-IN_2") (pintype "input"))
    )
    (net (code "110") (name "Net-(U14A-OUT)") (class "Default")
      (node (ref "C6") (pin "2") (pinfunction "2_2") (pintype "passive"))
      (node (ref "R39") (pin "2") (pinfunction "2_2") (pintype "passive"))
      (node (ref "R42") (pin "1") (pinfunction "1_1") (pintype "passive"))
      (node (ref "U14") (pin "1") (pinfunction "OUT_1") (pintype "output"))
    )
    (net (code "111") (name "Net-(U14B--IN)") (class "Default")
      (node (ref "C7") (pin "1") (pinfunction "1_1") (pintype "passive"))
      (node (ref "R40") (pin "2") (pinfunction "2_2") (pintype "passive"))
      (node (ref "R41") (pin "1") (pinfunction "1_1") (pintype "passive"))
      (node (ref "U14") (pin "6") (pinfunction "-IN_6") (pintype "input"))
    )
    (net (code "112") (name "Net-(U14B-OUT)") (class "Default")
      (node (ref "C7") (pin "2") (pinfunction "2_2") (pintype "passive"))
      (node (ref "R41") (pin "2") (pinfunction "2_2") (pintype "passive"))
      (node (ref "R44") (pin "1") (pinfunction "1_1") (pintype "passive"))
      (node (ref "U14") (pin "7") (pinfunction "OUT_7") (pintype "output"))
    )
    (net (code "113") (name "Net-(U14C--IN)") (class "Default")
      (node (ref "C18") (pin "1") (pinfunction "1_1") (pintype "passive"))
      (node (ref "R44") (pin "2") (pinfunction "2_2") (pintype "passive"))
      (node (ref "R45") (pin "1") (pinfunction "1_1") (pintype "passive"))
      (node (ref "U14") (pin "9") (pinfunction "-IN_9") (pintype "input"))
    )
    (net (code "114") (name "Net-(U14C-OUT)") (class "Default")
      (node (ref "C18") (pin "2") (pinfunction "2_2") (pintype "passive"))
      (node (ref "R45") (pin "2") (pinfunction "2_2") (pintype "passive"))
      (node (ref "R47") (pin "1") (pinfunction "1_1") (pintype "passive"))
      (node (ref "U14") (pin "8") (pinfunction "OUT_8") (pintype "output"))
    )
    (net (code "115") (name "Net-(U14D--IN)") (class "Default")
      (node (ref "C17") (pin "1") (pinfunction "1_1") (pintype "passive"))
      (node (ref "R42") (pin "2") (pinfunction "2_2") (pintype "passive"))
      (node (ref "R43") (pin "1") (pinfunction "1_1") (pintype "passive"))
      (node (ref "U14") (pin "13") (pinfunction "-IN_13") (pintype "input"))
    )
    (net (code "116") (name "Net-(U14D-OUT)") (class "Default")
      (node (ref "C17") (pin "2") (pinfunction "2_2") (pintype "passive"))
      (node (ref "R43") (pin "2") (pinfunction "2_2") (pintype "passive"))
      (node (ref "R46") (pin "1") (pinfunction "1_1") (pintype "passive"))
      (node (ref "U14") (pin "14") (pinfunction "OUT_14") (pintype "output"))
    )
    (net (code "117") (name "Net-(U15-A)") (class "Default")
      (node (ref "D5") (pin "C") (pinfunction "C_C") (pintype "passive"))
      (node (ref "R63") (pin "1") (pinfunction "1_1") (pintype "passive"))
      (node (ref "U15") (pin "1") (pinfunction "A_1") (pintype "bidirectional"))
    )
    (net (code "118") (name "Net-(U16A--IN)") (class "Default")
      (node (ref "C25") (pin "1") (pinfunction "1_1") (pintype "passive"))
      (node (ref "R52") (pin "1") (pinfunction "1_1") (pintype "passive"))
      (node (ref "R57") (pin "2") (pinfunction "2_2") (pintype "passive"))
      (node (ref "U16") (pin "2") (pinfunction "-IN_2") (pintype "input"))
    )
    (net (code "119") (name "Net-(U16A-OUT)") (class "Default")
      (node (ref "C25") (pin "2") (pinfunction "2_2") (pintype "passive"))
      (node (ref "R52") (pin "2") (pinfunction "2_2") (pintype "passive"))
      (node (ref "R54") (pin "1") (pinfunction "1_1") (pintype "passive"))
      (node (ref "U16") (pin "1") (pinfunction "OUT_1") (pintype "output"))
    )
    (net (code "120") (name "Net-(U16B--IN)") (class "Default")
      (node (ref "C28") (pin "1") (pinfunction "1_1") (pintype "passive"))
      (node (ref "R53") (pin "1") (pinfunction "1_1") (pintype "passive"))
      (node (ref "R59") (pin "2") (pinfunction "2_2") (pintype "passive"))
      (node (ref "U16") (pin "6") (pinfunction "-IN_6") (pintype "input"))
    )
    (net (code "121") (name "Net-(U16B-OUT)") (class "Default")
      (node (ref "C28") (pin "2") (pinfunction "2_2") (pintype "passive"))
      (node (ref "R53") (pin "2") (pinfunction "2_2") (pintype "passive"))
      (node (ref "R58") (pin "1") (pinfunction "1_1") (pintype "passive"))
      (node (ref "U16") (pin "7") (pinfunction "OUT_7") (pintype "output"))
    )
    (net (code "122") (name "Net-(U16C--IN)") (class "Default")
      (node (ref "C19") (pin "1") (pinfunction "1_1") (pintype "passive"))
      (node (ref "R50") (pin "1") (pinfunction "1_1") (pintype "passive"))
      (node (ref "R58") (pin "2") (pinfunction "2_2") (pintype "passive"))
      (node (ref "U16") (pin "9") (pinfunction "-IN_9") (pintype "input"))
    )
    (net (code "123") (name "Net-(U16C-OUT)") (class "Default")
      (node (ref "C19") (pin "2") (pinfunction "2_2") (pintype "passive"))
      (node (ref "R50") (pin "2") (pinfunction "2_2") (pintype "passive"))
      (node (ref "R51") (pin "1") (pinfunction "1_1") (pintype "passive"))
      (node (ref "U16") (pin "8") (pinfunction "OUT_8") (pintype "output"))
    )
    (net (code "124") (name "Net-(U16D--IN)") (class "Default")
      (node (ref "C24") (pin "1") (pinfunction "1_1") (pintype "passive"))
      (node (ref "R48") (pin "1") (pinfunction "1_1") (pintype "passive"))
      (node (ref "R54") (pin "2") (pinfunction "2_2") (pintype "passive"))
      (node (ref "U16") (pin "13") (pinfunction "-IN_13") (pintype "input"))
    )
    (net (code "125") (name "Net-(U16D-OUT)") (class "Default")
      (node (ref "C24") (pin "2") (pinfunction "2_2") (pintype "passive"))
      (node (ref "R48") (pin "2") (pinfunction "2_2") (pintype "passive"))
      (node (ref "R49") (pin "1") (pinfunction "1_1") (pintype "passive"))
      (node (ref "U16") (pin "14") (pinfunction "OUT_14") (pintype "output"))
    )
    (net (code "126") (name "OLED_CMD") (class "Default")
      (node (ref "U_DAISY") (pin "10") (pinfunction "GPIO10(SPI1_MISO)_10") (pintype "bidirectional"))
      (node (ref "U_DAISY") (pin "B10") (pinfunction "GPIO10(SPI1_MISO)_B10") (pintype "bidirectional"))
      (node (ref "U_OLED") (pin "6") (pinfunction "DC_6") (pintype "bidirectional"))
    )
    (net (code "127") (name "OLED_CS") (class "Default")
      (node (ref "U_DAISY") (pin "8") (pinfunction "GPIO8(SPI1_NSS)_8") (pintype "bidirectional"))
      (node (ref "U_DAISY") (pin "B8") (pinfunction "GPIO8(SPI1_NSS)_B8") (pintype "bidirectional"))
      (node (ref "U_OLED") (pin "7") (pinfunction "CS_7") (pintype "bidirectional"))
    )
    (net (code "128") (name "OLED_DATA") (class "Default")
      (node (ref "U_DAISY") (pin "11") (pinfunction "GPIO11(SPI1_MOSI)_11") (pintype "bidirectional"))
      (node (ref "U_DAISY") (pin "B11") (pinfunction "GPIO11(SPI1_MOSI)_B11") (pintype "bidirectional"))
      (node (ref "U_OLED") (pin "4") (pinfunction "SDA_4") (pintype "bidirectional"))
    )
    (net (code "129") (name "OLED_RST") (class "Default")
      (node (ref "U_DAISY") (pin "37") (pinfunction "GPIO31(USB_HS_D+)_37") (pintype "bidirectional"))
      (node (ref "U_DAISY") (pin "B37") (pinfunction "GPIO31(USB_HS_D+)_B37") (pintype "bidirectional"))
      (node (ref "U_OLED") (pin "5") (pinfunction "RES_5") (pintype "bidirectional"))
    )
    (net (code "130") (name "OLED_SCK") (class "Default")
      (node (ref "U_DAISY") (pin "9") (pinfunction "GPIO9(SPI1_SCK)_9") (pintype "bidirectional"))
      (node (ref "U_DAISY") (pin "B9") (pinfunction "GPIO9(SPI1_SCK)_B9") (pintype "bidirectional"))
      (node (ref "U_OLED") (pin "3") (pinfunction "SCL_3") (pintype "bidirectional"))
    )
    (net (code "131") (name "SAI2_FS_A") (class "Default")
      (node (ref "U2") (pin "14") (pinfunction "LRCK_14") (pintype "bidirectional"))
      (node (ref "U_DAISY") (pin "34") (pinfunction "GPIO28(SAI2_FS_B)_34") (pintype "bidirectional"))
      (node (ref "U_DAISY") (pin "B34") (pinfunction "GPIO28(SAI2_FS_B)_B34") (pintype "bidirectional"))
    )
    (net (code "132") (name "SAI2_MCLK") (class "Default")
      (node (ref "U2") (pin "15") (pinfunction "MCLK_15") (pintype "bidirectional"))
      (node (ref "U_DAISY") (pin "31") (pinfunction "GPIO25(SAI2_MCLK_B)_31") (pintype "bidirectional"))
      (node (ref "U_DAISY") (pin "B31") (pinfunction "GPIO25(SAI2_MCLK_B)_B31") (pintype "bidirectional"))
    )
    (net (code "133") (name "SAI2_SCK_A") (class "Default")
      (node (ref "U2") (pin "16") (pinfunction "BCLK_16") (pintype "bidirectional"))
      (node (ref "U_DAISY") (pin "35") (pinfunction "GPIO29(SAI2_SCK_B)_35") (pintype "bidirectional"))
      (node (ref "U_DAISY") (pin "B35") (pinfunction "GPIO29(SAI2_SCK_B)_B35") (pintype "bidirectional"))
    )
    (net (code "134") (name "SAI2_SD_A") (class "Default")
      (node (ref "U2") (pin "13") (pinfunction "SDI_13") (pintype "bidirectional"))
      (node (ref "U_DAISY") (pin "33") (pinfunction "GPIO27(SAI2_SD_A)_33") (pintype "bidirectional"))
      (node (ref "U_DAISY") (pin "B33") (pinfunction "GPIO27(SAI2_SD_A)_B33") (pintype "bidirectional"))
    )
    (net (code "135") (name "SAI2_SD_B") (class "Default")
      (node (ref "U2") (pin "8") (pinfunction "SDO_8") (pintype "bidirectional"))
      (node (ref "U_DAISY") (pin "32") (pinfunction "GPIO26(SAI2_SD_B)_32") (pintype "bidirectional"))
      (node (ref "U_DAISY") (pin "B32") (pinfunction "GPIO26(SAI2_SD_B)_B32") (pintype "bidirectional"))
    )
    (net (code "136") (name "SD_CK") (class "Default")
      (node (ref "U3") (pin "P$5") (pinfunction "SCK_P$5") (pintype "bidirectional"))
      (node (ref "U_DAISY") (pin "7") (pinfunction "GPIO7(SDMMC1_CK)_7") (pintype "bidirectional"))
      (node (ref "U_DAISY") (pin "B7") (pinfunction "GPIO7(SDMMC1_CK)_B7") (pintype "bidirectional"))
    )
    (net (code "137") (name "SD_CMD") (class "Default")
      (node (ref "R5") (pin "1") (pinfunction "1_1") (pintype "passive"))
      (node (ref "U3") (pin "P$3") (pinfunction "CMD/DI_P$3") (pintype "bidirectional"))
      (node (ref "U_DAISY") (pin "6") (pinfunction "GPIO6(SDMMC1_CMD)_6") (pintype "bidirectional"))
      (node (ref "U_DAISY") (pin "B6") (pinfunction "GPIO6(SDMMC1_CMD)_B6") (pintype "bidirectional"))
    )
    (net (code "138") (name "SD_D0") (class "Default")
      (node (ref "R6") (pin "1") (pinfunction "1_1") (pintype "passive"))
      (node (ref "U3") (pin "P$7") (pinfunction "D0/DO_P$7") (pintype "bidirectional"))
      (node (ref "U_DAISY") (pin "5") (pinfunction "GPIO5(SDMMC1_D0)_5") (pintype "bidirectional"))
      (node (ref "U_DAISY") (pin "B5") (pinfunction "GPIO5(SDMMC1_D0)_B5") (pintype "bidirectional"))
    )
    (net (code "139") (name "SD_D1") (class "Default")
      (node (ref "R7") (pin "1") (pinfunction "1_1") (pintype "passive"))
      (node (ref "U3") (pin "P$8") (pinfunction "D1/RSV_P$8") (pintype "bidirectional"))
      (node (ref "U_DAISY") (pin "4") (pinfunction "GPIO4(SDMMC1_D1)_4") (pintype "bidirectional"))
      (node (ref "U_DAISY") (pin "B4") (pinfunction "GPIO4(SDMMC1_D1)_B4") (pintype "bidirectional"))
    )
    (net (code "140") (name "SD_D2") (class "Default")
      (node (ref "R3") (pin "1") (pinfunction "1_1") (pintype "passive"))
      (node (ref "U3") (pin "P$1") (pinfunction "D2/NC_P$1") (pintype "bidirectional"))
      (node (ref "U_DAISY") (pin "3") (pinfunction "GPIO3(SDMMC1_D2)_3") (pintype "bidirectional"))
      (node (ref "U_DAISY") (pin "B3") (pinfunction "GPIO3(SDMMC1_D2)_B3") (pintype "bidirectional"))
    )
    (net (code "141") (name "SD_D3") (class "Default")
      (node (ref "R4") (pin "1") (pinfunction "1_1") (pintype "passive"))
      (node (ref "U3") (pin "P$2") (pinfunction "D3/CS_P$2") (pintype "bidirectional"))
      (node (ref "U_DAISY") (pin "2") (pinfunction "GPIO2(SDMMC1_D3)_2") (pintype "bidirectional"))
      (node (ref "U_DAISY") (pin "B2") (pinfunction "GPIO2(SDMMC1_D3)_B2") (pintype "bidirectional"))
    )
    (net (code "142") (name "SPI1_MOSI_IN") (class "Default")
      (node (ref "J_GATE_IN_1") (pin "TIP") (pinfunction "TIP_TIP") (pintype "passive"))
      (node (ref "R21") (pin "1") (pinfunction "1_1") (pintype "passive"))
    )
    (net (code "143") (name "SPI1_NSS_OUT") (class "Default")
      (node (ref "J_GATE_OUT") (pin "TIP") (pinfunction "TIP_TIP") (pintype "passive"))
      (node (ref "R38") (pin "1") (pinfunction "1_1") (pintype "passive"))
    )
    (net (code "144") (name "USART1_RX") (class "Default")
      (node (ref "R64") (pin "2") (pinfunction "2_2") (pintype "passive"))
      (node (ref "U15") (pin "4") (pinfunction "OUT_4") (pintype "bidirectional"))
      (node (ref "U_DAISY") (pin "15") (pinfunction "GPIO15(USART1_RX)_15") (pintype "bidirectional"))
      (node (ref "U_DAISY") (pin "B15") (pinfunction "GPIO15(USART1_RX)_B15") (pintype "bidirectional"))
    )
    (net (code "145") (name "USART1_TX") (class "Default")
      (node (ref "R2") (pin "2") (pinfunction "2_2") (pintype "passive"))
      (node (ref "U_DAISY") (pin "14") (pinfunction "GPIO14(USART1_TX)_14") (pintype "bidirectional"))
      (node (ref "U_DAISY") (pin "B14") (pinfunction "GPIO14(USART1_TX)_B14") (pintype "bidirectional"))
    )
    (net (code "146") (name "unconnected-(J_AUDIO_IN_1-PadNORM)") (class "Default")
      (node (ref "J_AUDIO_IN_1") (pin "NORM") (pinfunction "NORM_NORM") (pintype "passive"))
    )
    (net (code "147") (name "unconnected-(J_AUDIO_OUT_1-PadNORM)") (class "Default")
      (node (ref "J_AUDIO_OUT_1") (pin "NORM") (pinfunction "NORM_NORM") (pintype "passive"))
    )
    (net (code "148") (name "unconnected-(J_AUDIO_OUT_2-PadNORM)") (class "Default")
      (node (ref "J_AUDIO_OUT_2") (pin "NORM") (pinfunction "NORM_NORM") (pintype "passive"))
    )
    (net (code "149") (name "unconnected-(J_AUDIO_OUT_3-PadNORM)") (class "Default")
      (node (ref "J_AUDIO_OUT_3") (pin "NORM") (pinfunction "NORM_NORM") (pintype "passive"))
    )
    (net (code "150") (name "unconnected-(J_AUDIO_OUT_4-PadNORM)") (class "Default")
      (node (ref "J_AUDIO_OUT_4") (pin "NORM") (pinfunction "NORM_NORM") (pintype "passive"))
    )
    (net (code "151") (name "unconnected-(J_CV_1-PadNORM)") (class "Default")
      (node (ref "J_CV_1") (pin "NORM") (pinfunction "NORM_NORM") (pintype "passive"))
    )
    (net (code "152") (name "unconnected-(J_CV_2-PadNORM)") (class "Default")
      (node (ref "J_CV_2") (pin "NORM") (pinfunction "NORM_NORM") (pintype "passive"))
    )
    (net (code "153") (name "unconnected-(J_CV_3-PadNORM)") (class "Default")
      (node (ref "J_CV_3") (pin "NORM") (pinfunction "NORM_NORM") (pintype "passive"))
    )
    (net (code "154") (name "unconnected-(J_CV_4-PadNORM)") (class "Default")
      (node (ref "J_CV_4") (pin "NORM") (pinfunction "NORM_NORM") (pintype "passive"))
    )
    (net (code "155") (name "unconnected-(J_CV_OUT_1-PadNORM)") (class "Default")
      (node (ref "J_CV_OUT_1") (pin "NORM") (pinfunction "NORM_NORM") (pintype "passive"))
    )
    (net (code "156") (name "unconnected-(J_CV_OUT_2-PadNORM)") (class "Default")
      (node (ref "J_CV_OUT_2") (pin "NORM") (pinfunction "NORM_NORM") (pintype "passive"))
    )
    (net (code "157") (name "unconnected-(J_GATE_IN_1-PadNORM)") (class "Default")
      (node (ref "J_GATE_IN_1") (pin "NORM") (pinfunction "NORM_NORM") (pintype "passive"))
    )
    (net (code "158") (name "unconnected-(J_GATE_IN_2-PadNORM)") (class "Default")
      (node (ref "J_GATE_IN_2") (pin "NORM") (pinfunction "NORM_NORM") (pintype "passive"))
    )
    (net (code "159") (name "unconnected-(J_GATE_OUT-PadNORM)") (class "Default")
      (node (ref "J_GATE_OUT") (pin "NORM") (pinfunction "NORM_NORM") (pintype "passive"))
    )
  )
)
